# module.net
KiCad netlist of a schematic drawn in EAGLE
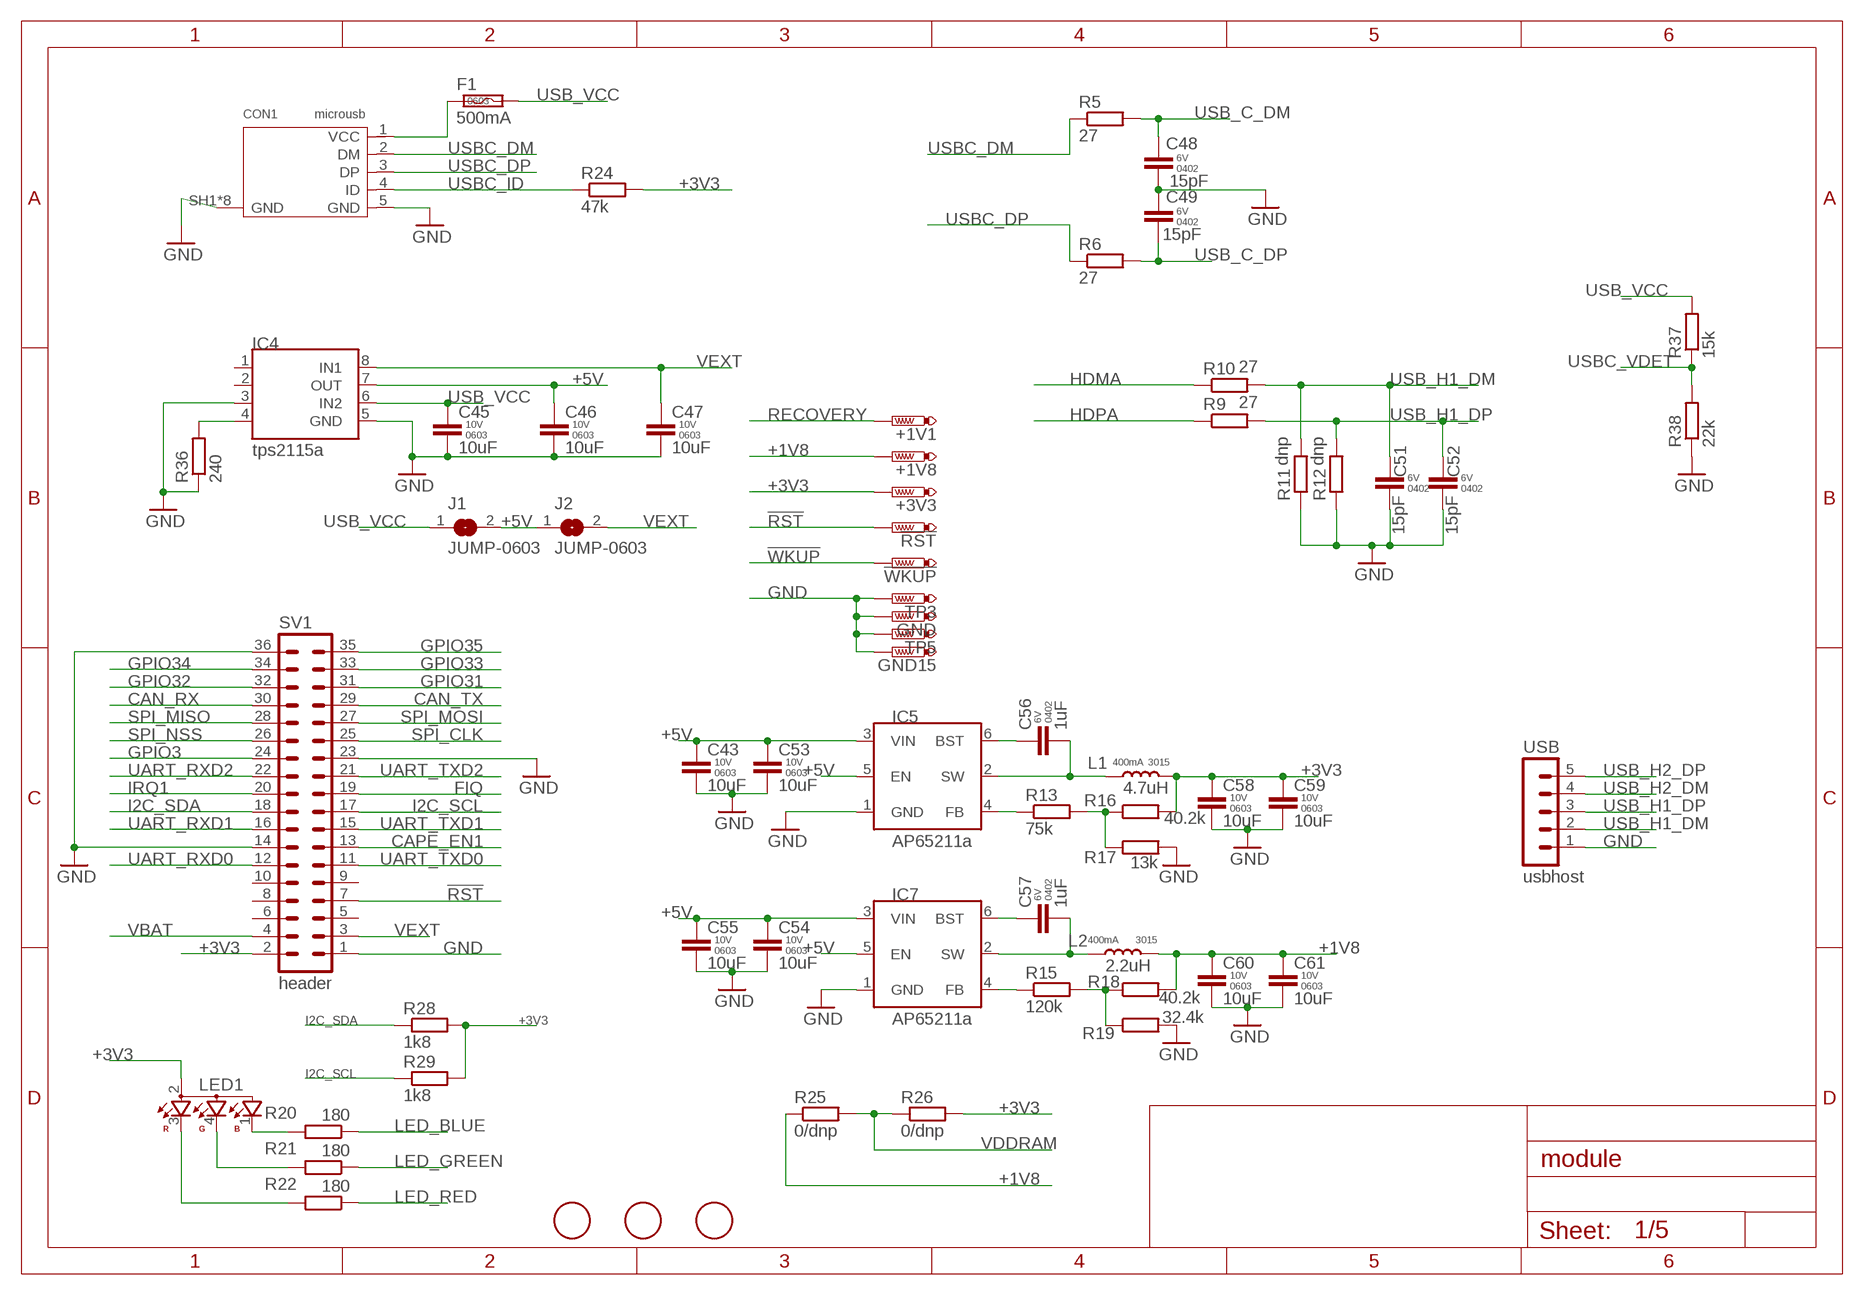
[diagram p0: schematic, sheet 1]
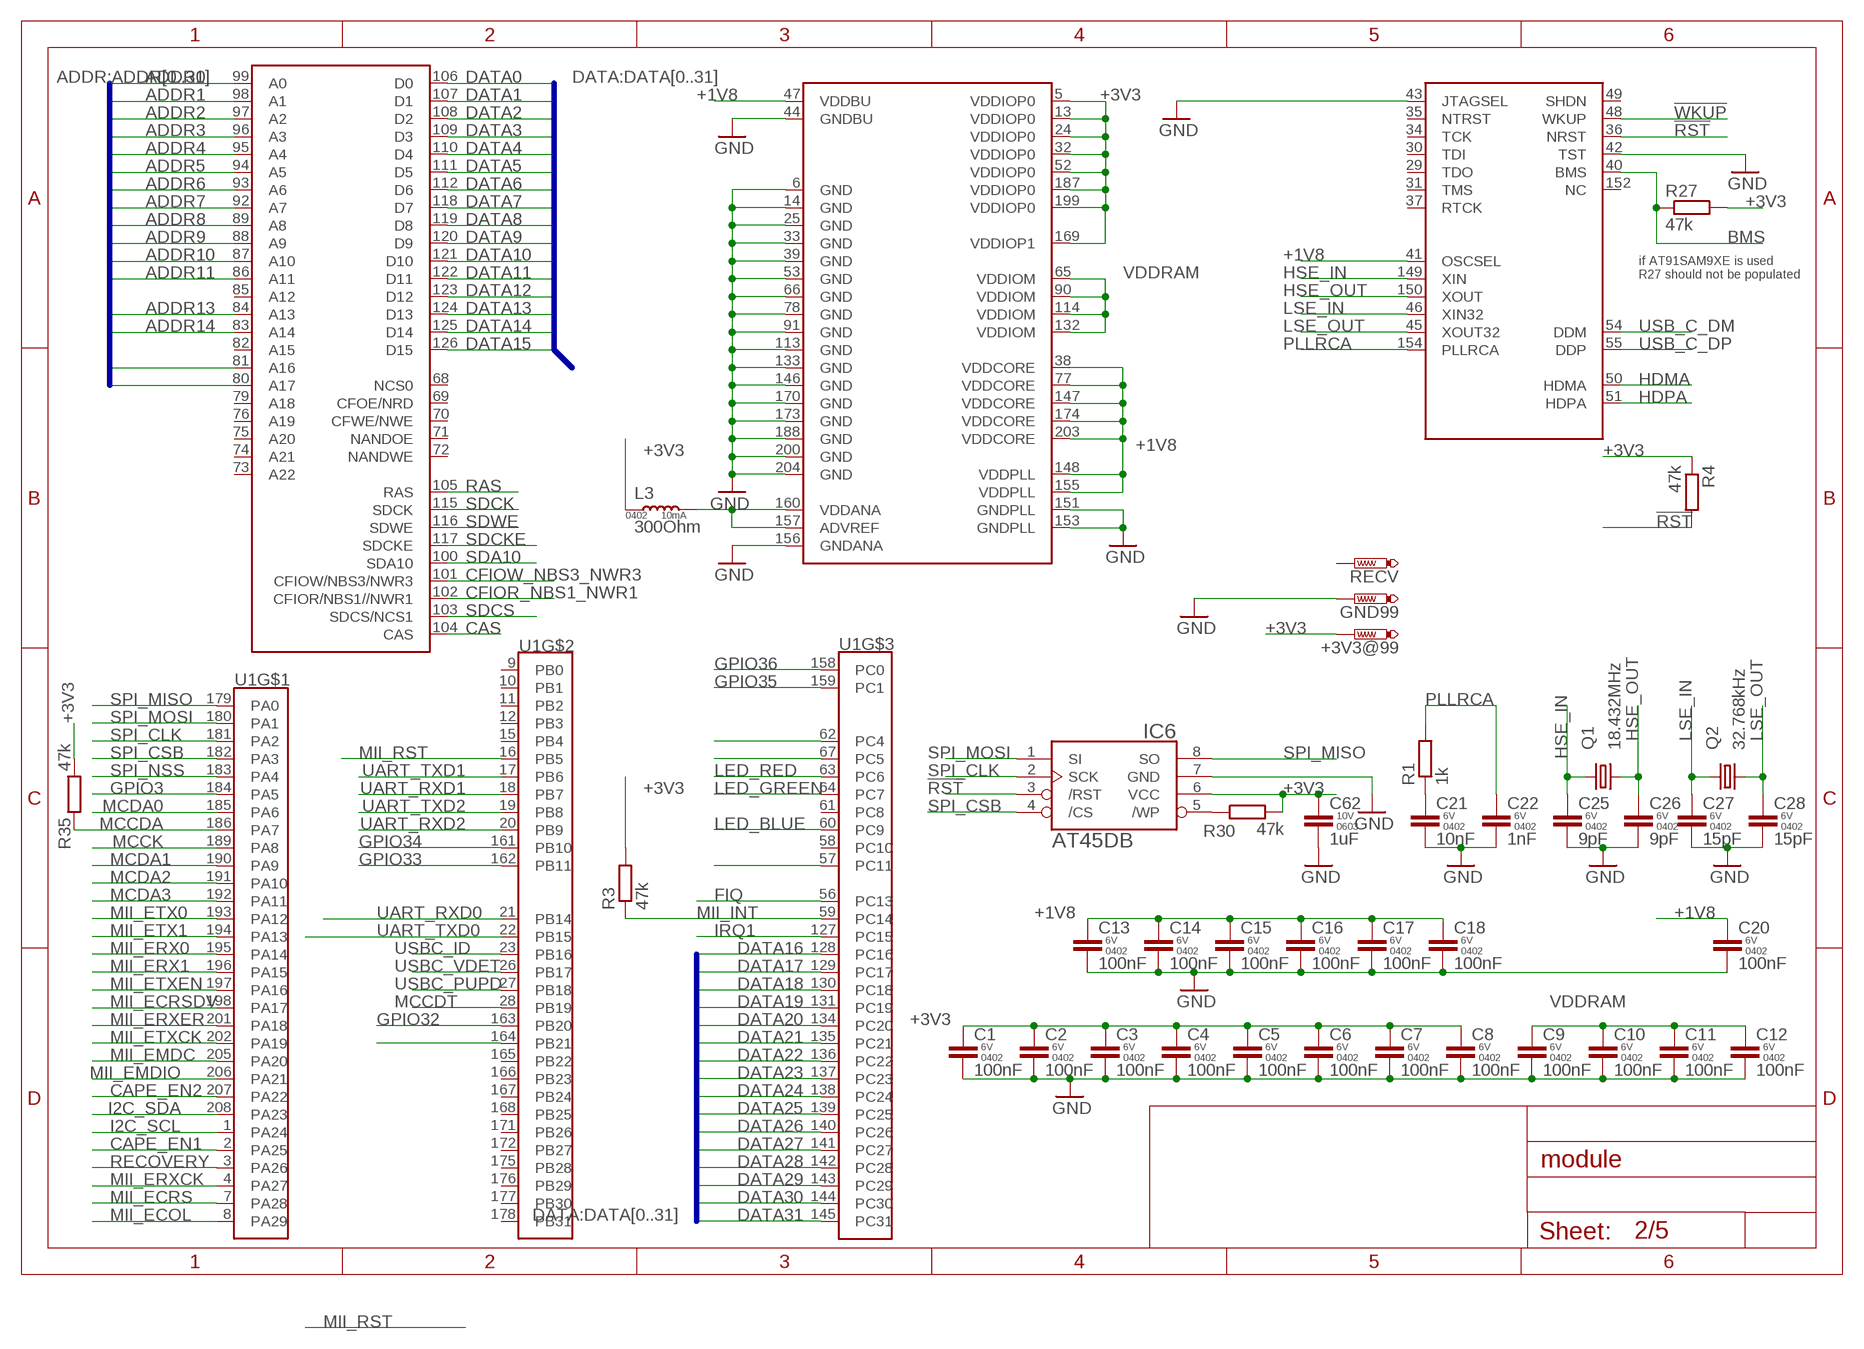
[diagram p1: schematic, sheet 2]
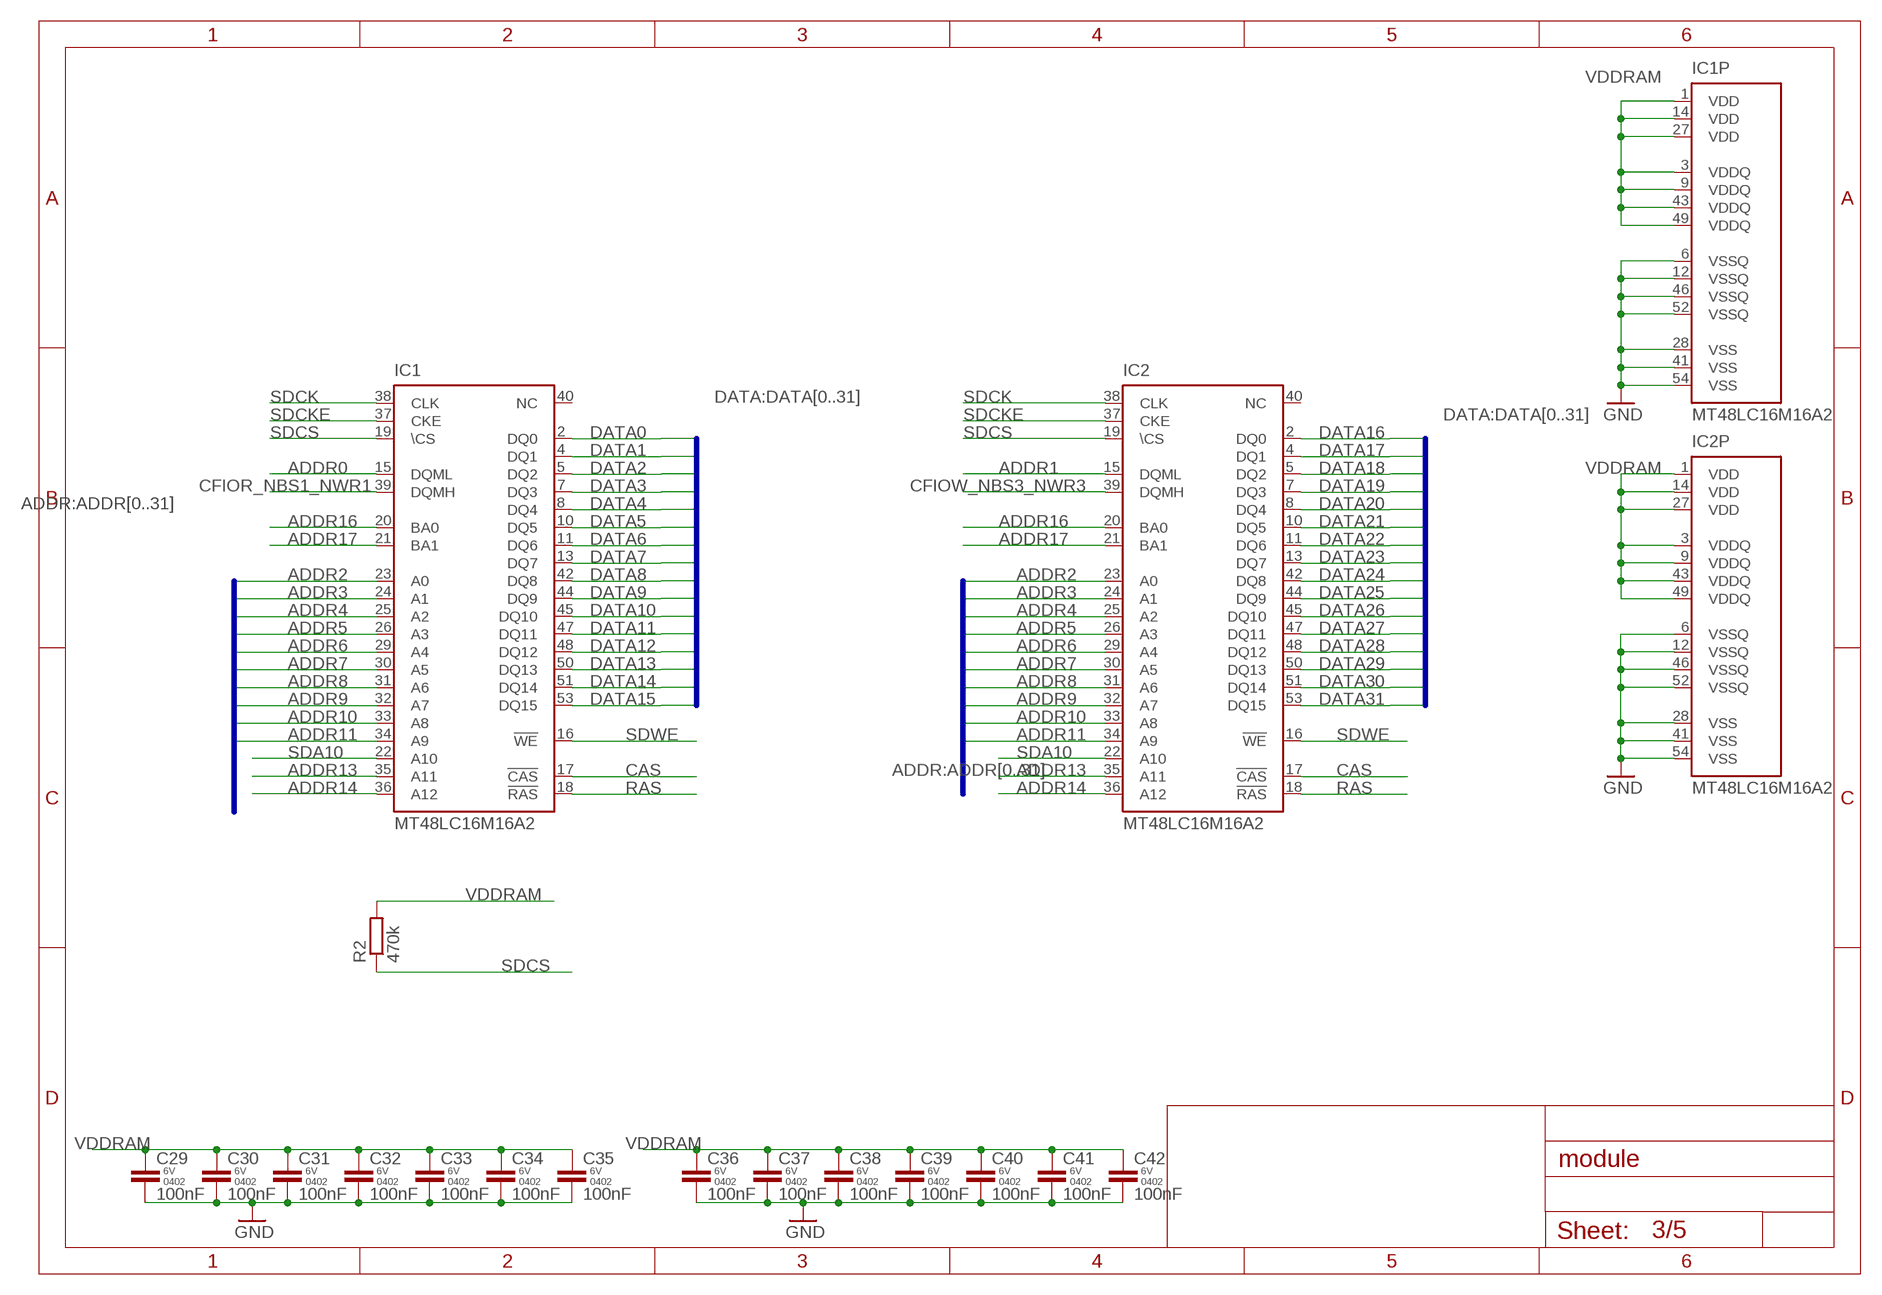
[diagram p2: schematic, sheet 3]
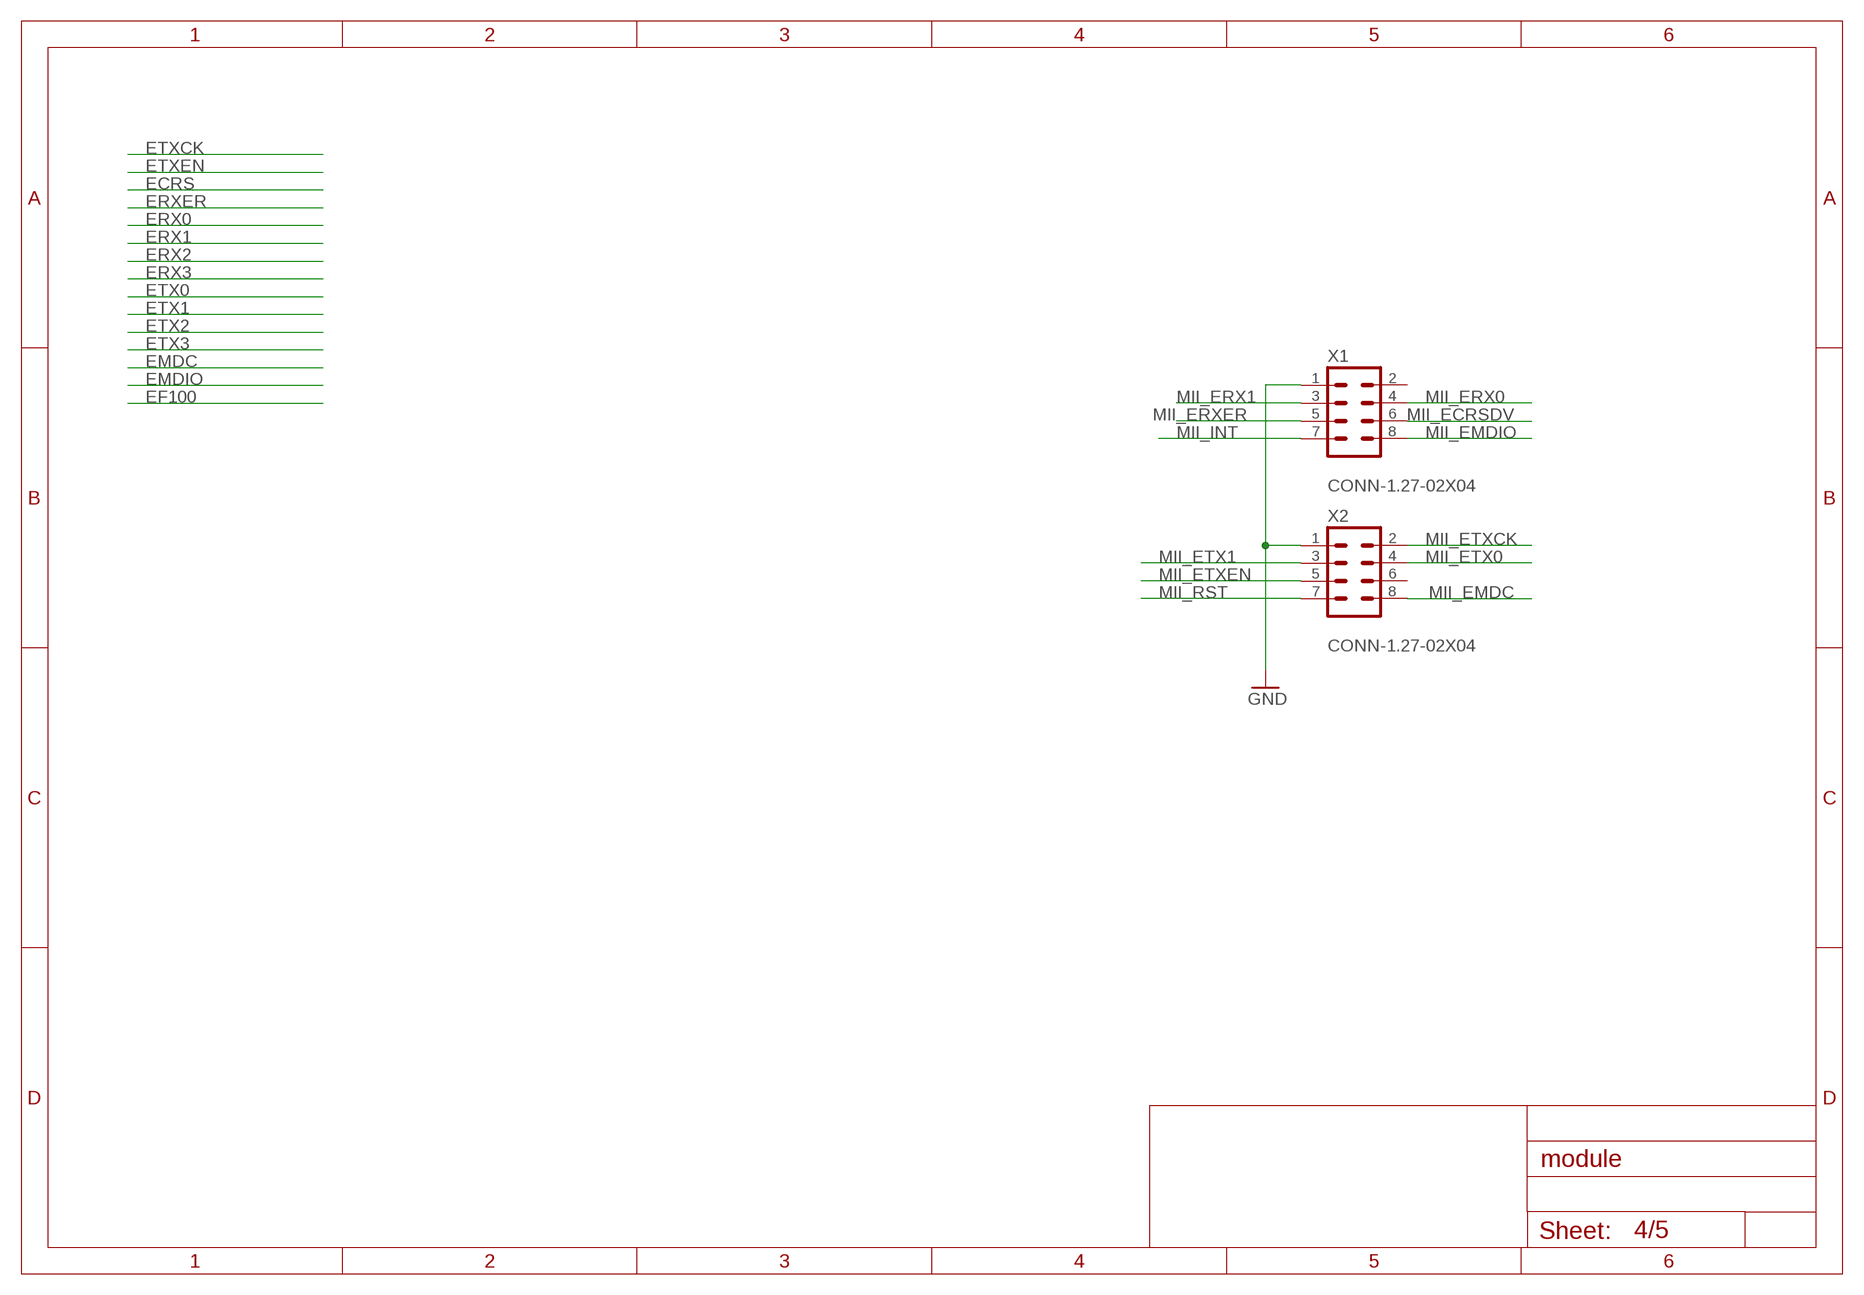
[diagram p3: schematic, sheet 4]
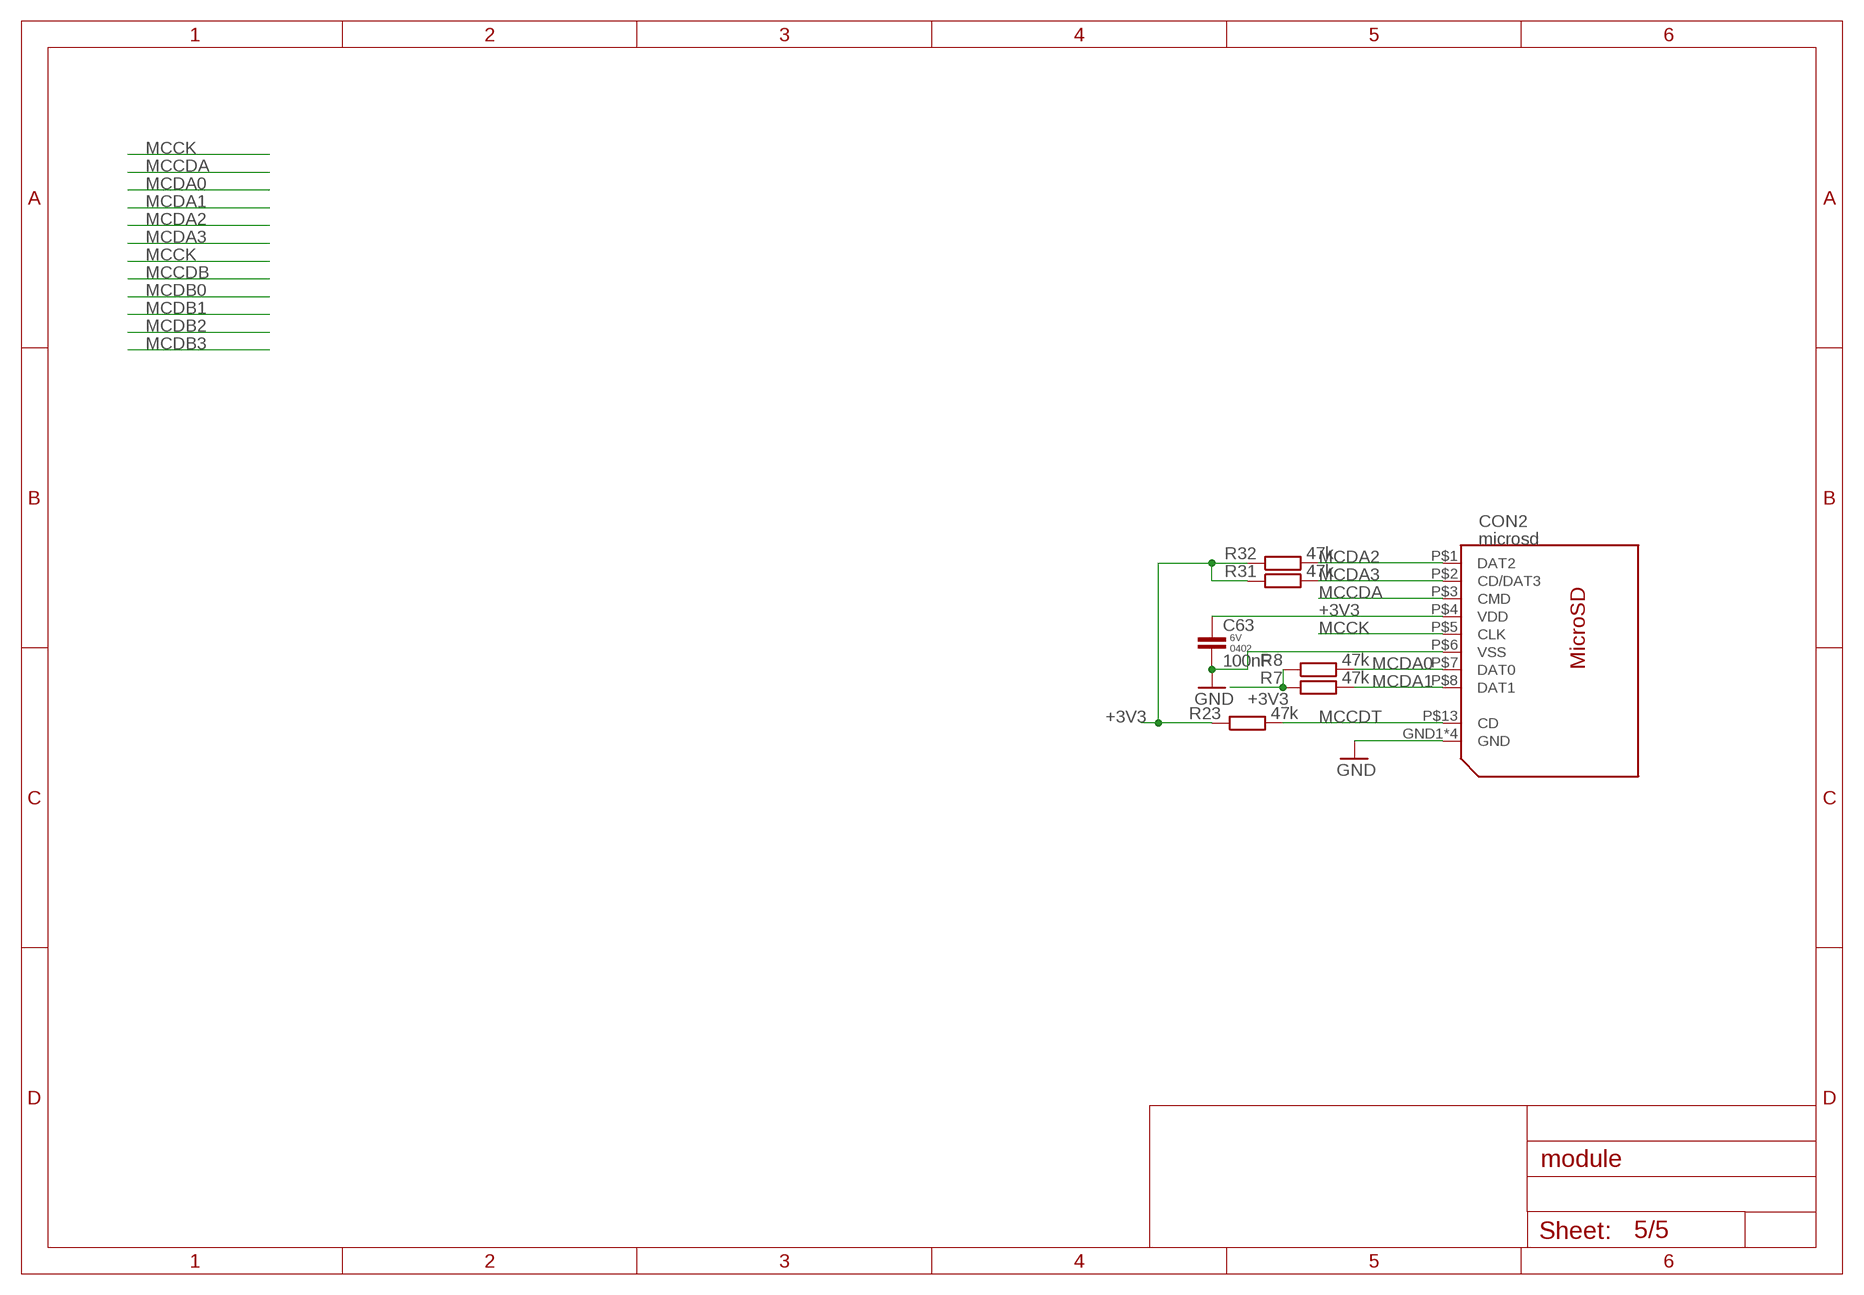
[diagram p4: schematic, sheet 5]

(export (version "E")
  (design (tool "Eeschema 10.0.6"))
  (components
    (comp (ref "C29")
      (value "100nF")
      (footprint "eagle-import:C0402K")
      (fields (field (name "RATING") "6V") (field (name "PACKAGE") "0402"))
      (libsource (lib "eagle-import") (part "CAP-0402"))
    )
    (comp (ref "C30")
      (value "100nF")
      (footprint "eagle-import:C0402K")
      (fields (field (name "RATING") "6V") (field (name "PACKAGE") "0402"))
      (libsource (lib "eagle-import") (part "CAP-0402"))
    )
    (comp (ref "C31")
      (value "100nF")
      (footprint "eagle-import:C0402K")
      (fields (field (name "RATING") "6V") (field (name "PACKAGE") "0402"))
      (libsource (lib "eagle-import") (part "CAP-0402"))
    )
    (comp (ref "C32")
      (value "100nF")
      (footprint "eagle-import:C0402K")
      (fields (field (name "RATING") "6V") (field (name "PACKAGE") "0402"))
      (libsource (lib "eagle-import") (part "CAP-0402"))
    )
    (comp (ref "C33")
      (value "100nF")
      (footprint "eagle-import:C0402K")
      (fields (field (name "RATING") "6V") (field (name "PACKAGE") "0402"))
      (libsource (lib "eagle-import") (part "CAP-0402"))
    )
    (comp (ref "C34")
      (value "100nF")
      (footprint "eagle-import:C0402K")
      (fields (field (name "RATING") "6V") (field (name "PACKAGE") "0402"))
      (libsource (lib "eagle-import") (part "CAP-0402"))
    )
    (comp (ref "C35")
      (value "100nF")
      (footprint "eagle-import:C0402K")
      (fields (field (name "RATING") "6V") (field (name "PACKAGE") "0402"))
      (libsource (lib "eagle-import") (part "CAP-0402"))
    )
    (comp (ref "C36")
      (value "100nF")
      (footprint "eagle-import:C0402K")
      (fields (field (name "RATING") "6V") (field (name "PACKAGE") "0402"))
      (libsource (lib "eagle-import") (part "CAP-0402"))
    )
    (comp (ref "C37")
      (value "100nF")
      (footprint "eagle-import:C0402K")
      (fields (field (name "RATING") "6V") (field (name "PACKAGE") "0402"))
      (libsource (lib "eagle-import") (part "CAP-0402"))
    )
    (comp (ref "C38")
      (value "100nF")
      (footprint "eagle-import:C0402K")
      (fields (field (name "RATING") "6V") (field (name "PACKAGE") "0402"))
      (libsource (lib "eagle-import") (part "CAP-0402"))
    )
    (comp (ref "C39")
      (value "100nF")
      (footprint "eagle-import:C0402K")
      (fields (field (name "RATING") "6V") (field (name "PACKAGE") "0402"))
      (libsource (lib "eagle-import") (part "CAP-0402"))
    )
    (comp (ref "C40")
      (value "100nF")
      (footprint "eagle-import:C0402K")
      (fields (field (name "RATING") "6V") (field (name "PACKAGE") "0402"))
      (libsource (lib "eagle-import") (part "CAP-0402"))
    )
    (comp (ref "C41")
      (value "100nF")
      (footprint "eagle-import:C0402K")
      (fields (field (name "RATING") "6V") (field (name "PACKAGE") "0402"))
      (libsource (lib "eagle-import") (part "CAP-0402"))
    )
    (comp (ref "C42")
      (value "100nF")
      (footprint "eagle-import:C0402K")
      (fields (field (name "RATING") "6V") (field (name "PACKAGE") "0402"))
      (libsource (lib "eagle-import") (part "CAP-0402"))
    )
    (comp (ref "IC1")
      (value "MT48LC16M16A2")
      (footprint "eagle-import:TSOP54-400")
      (libsource (lib "eagle-import") (part "MT48LC16M16A2"))
    )
    (comp (ref "IC2")
      (value "MT48LC16M16A2")
      (footprint "eagle-import:TSOP54-400")
      (libsource (lib "eagle-import") (part "MT48LC16M16A2"))
    )
    (comp (ref "R2")
      (value "470k")
      (footprint "eagle-import:R0402")
      (libsource (lib "eagle-import") (part "R-EU_R0402"))
    )
    (comp (ref "!RST")
      (value "PTR1B1,27")
      (footprint "eagle-import:B1,27")
      (libsource (lib "eagle-import") (part "PTR1B1,27"))
    )
    (comp (ref "!WKUP")
      (value "PTR1B1,27")
      (footprint "eagle-import:B1,27")
      (libsource (lib "eagle-import") (part "PTR1B1,27"))
    )
    (comp (ref "+1V1")
      (value "PTR1B1,27")
      (footprint "eagle-import:B1,27")
      (libsource (lib "eagle-import") (part "PTR1B1,27"))
    )
    (comp (ref "+1V8")
      (value "PTR1B1,27")
      (footprint "eagle-import:B1,27")
      (libsource (lib "eagle-import") (part "PTR1B1,27"))
    )
    (comp (ref "+3V3")
      (value "PTR1B1,27")
      (footprint "eagle-import:B1,27")
      (libsource (lib "eagle-import") (part "PTR1B1,27"))
    )
    (comp (ref "C43")
      (value "10uF")
      (footprint "eagle-import:C0603")
      (fields (field (name "RATING") "10V") (field (name "PACKAGE") "0603"))
      (libsource (lib "eagle-import") (part "CAP-0603"))
    )
    (comp (ref "C45")
      (value "10uF")
      (footprint "eagle-import:C0603")
      (fields (field (name "RATING") "10V") (field (name "PACKAGE") "0603"))
      (libsource (lib "eagle-import") (part "CAP-0603"))
    )
    (comp (ref "C46")
      (value "10uF")
      (footprint "eagle-import:C0603")
      (fields (field (name "RATING") "10V") (field (name "PACKAGE") "0603"))
      (libsource (lib "eagle-import") (part "CAP-0603"))
    )
    (comp (ref "C47")
      (value "10uF")
      (footprint "eagle-import:C0603")
      (fields (field (name "RATING") "10V") (field (name "PACKAGE") "0603"))
      (libsource (lib "eagle-import") (part "CAP-0603"))
    )
    (comp (ref "C48")
      (value "15pF")
      (footprint "eagle-import:C0402K")
      (fields (field (name "RATING") "6V") (field (name "PACKAGE") "0402"))
      (libsource (lib "eagle-import") (part "CAP-0402"))
    )
    (comp (ref "C49")
      (value "15pF")
      (footprint "eagle-import:C0402K")
      (fields (field (name "RATING") "6V") (field (name "PACKAGE") "0402"))
      (libsource (lib "eagle-import") (part "CAP-0402"))
    )
    (comp (ref "C51")
      (value "15pF")
      (footprint "eagle-import:C0402K")
      (fields (field (name "RATING") "6V") (field (name "PACKAGE") "0402"))
      (libsource (lib "eagle-import") (part "CAP-0402"))
    )
    (comp (ref "C52")
      (value "15pF")
      (footprint "eagle-import:C0402K")
      (fields (field (name "RATING") "6V") (field (name "PACKAGE") "0402"))
      (libsource (lib "eagle-import") (part "CAP-0402"))
    )
    (comp (ref "C53")
      (value "10uF")
      (footprint "eagle-import:C0603")
      (fields (field (name "RATING") "10V") (field (name "PACKAGE") "0603"))
      (libsource (lib "eagle-import") (part "CAP-0603"))
    )
    (comp (ref "C54")
      (value "10uF")
      (footprint "eagle-import:C0603")
      (fields (field (name "RATING") "10V") (field (name "PACKAGE") "0603"))
      (libsource (lib "eagle-import") (part "CAP-0603"))
    )
    (comp (ref "C55")
      (value "10uF")
      (footprint "eagle-import:C0603")
      (fields (field (name "RATING") "10V") (field (name "PACKAGE") "0603"))
      (libsource (lib "eagle-import") (part "CAP-0603"))
    )
    (comp (ref "C56")
      (value "1uF")
      (footprint "eagle-import:C0402K")
      (fields (field (name "RATING") "6V") (field (name "PACKAGE") "0402"))
      (libsource (lib "eagle-import") (part "CAP-0402"))
    )
    (comp (ref "C57")
      (value "1uF")
      (footprint "eagle-import:C0402K")
      (fields (field (name "RATING") "6V") (field (name "PACKAGE") "0402"))
      (libsource (lib "eagle-import") (part "CAP-0402"))
    )
    (comp (ref "C58")
      (value "10uF")
      (footprint "eagle-import:C0603")
      (fields (field (name "RATING") "10V") (field (name "PACKAGE") "0603"))
      (libsource (lib "eagle-import") (part "CAP-0603"))
    )
    (comp (ref "C59")
      (value "10uF")
      (footprint "eagle-import:C0603")
      (fields (field (name "RATING") "10V") (field (name "PACKAGE") "0603"))
      (libsource (lib "eagle-import") (part "CAP-0603"))
    )
    (comp (ref "C60")
      (value "10uF")
      (footprint "eagle-import:C0603")
      (fields (field (name "RATING") "10V") (field (name "PACKAGE") "0603"))
      (libsource (lib "eagle-import") (part "CAP-0603"))
    )
    (comp (ref "C61")
      (value "10uF")
      (footprint "eagle-import:C0603")
      (fields (field (name "RATING") "10V") (field (name "PACKAGE") "0603"))
      (libsource (lib "eagle-import") (part "CAP-0603"))
    )
    (comp (ref "CON1")
      (value "microusb")
      (footprint "eagle-import:10118194")
      (libsource (lib "eagle-import") (part "10118194-0001LF"))
    )
    (comp (ref "F1")
      (value "500mA")
      (footprint "eagle-import:F0603")
      (fields (field (name "PACKAGE") "0603"))
      (libsource (lib "eagle-import") (part "FUSE-PTC-0603"))
    )
    (comp (ref "GND")
      (value "PTR1B1,27")
      (footprint "eagle-import:B1,27")
      (libsource (lib "eagle-import") (part "PTR1B1,27"))
    )
    (comp (ref "GND15")
      (value "PTR1B1,27")
      (footprint "eagle-import:B1,27")
      (libsource (lib "eagle-import") (part "PTR1B1,27"))
    )
    (comp (ref "IC4")
      (value "tps2115a")
      (footprint "eagle-import:TSSOP8")
      (libsource (lib "eagle-import") (part "TPS2115A"))
    )
    (comp (ref "IC5")
      (value "AP65211")
      (footprint "eagle-import:SOT95P280X110-6")
      (libsource (lib "eagle-import") (part "AP65211"))
    )
    (comp (ref "IC7")
      (value "AP65211")
      (footprint "eagle-import:SOT95P280X110-6")
      (libsource (lib "eagle-import") (part "AP65211"))
    )
    (comp (ref "J1")
      (value "JUMP-0603")
      (footprint "eagle-import:C0603")
      (libsource (lib "eagle-import") (part "JUMP-0603"))
    )
    (comp (ref "J2")
      (value "JUMP-0603")
      (footprint "eagle-import:C0603")
      (libsource (lib "eagle-import") (part "JUMP-0603"))
    )
    (comp (ref "L1")
      (value "4.7uH")
      (footprint "eagle-import:L3230M")
      (fields (field (name "PACKAGE") "3015") (field (name "CURRENT") "400mA"))
      (libsource (lib "eagle-import") (part "DJNR3015"))
    )
    (comp (ref "L2")
      (value "2.2uH")
      (footprint "eagle-import:L3230M")
      (fields (field (name "PACKAGE") "3015") (field (name "CURRENT") "400mA"))
      (libsource (lib "eagle-import") (part "DJNR3015"))
    )
    (comp (ref "LED1")
      (value "OSTB1204C1E")
      (footprint "eagle-import:321015RGB")
      (libsource (lib "eagle-import") (part "OSTB1204C1E"))
    )
    (comp (ref "R5")
      (value "27")
      (footprint "eagle-import:R0402")
      (libsource (lib "eagle-import") (part "R-EU_R0402"))
    )
    (comp (ref "R6")
      (value "27")
      (footprint "eagle-import:R0402")
      (libsource (lib "eagle-import") (part "R-EU_R0402"))
    )
    (comp (ref "R9")
      (value "27")
      (footprint "eagle-import:R0402")
      (libsource (lib "eagle-import") (part "R-EU_R0402"))
    )
    (comp (ref "R10")
      (value "27")
      (footprint "eagle-import:R0402")
      (libsource (lib "eagle-import") (part "R-EU_R0402"))
    )
    (comp (ref "R11")
      (value "dnp")
      (footprint "eagle-import:R0402")
      (libsource (lib "eagle-import") (part "R-EU_R0402"))
    )
    (comp (ref "R12")
      (value "dnp")
      (footprint "eagle-import:R0402")
      (libsource (lib "eagle-import") (part "R-EU_R0402"))
    )
    (comp (ref "R13")
      (value "75k")
      (footprint "eagle-import:R0402")
      (libsource (lib "eagle-import") (part "R-EU_R0402"))
    )
    (comp (ref "R15")
      (value "120k")
      (footprint "eagle-import:R0402")
      (libsource (lib "eagle-import") (part "R-EU_R0402"))
    )
    (comp (ref "R16")
      (value "40.2k")
      (footprint "eagle-import:R0402")
      (libsource (lib "eagle-import") (part "R-EU_R0402"))
    )
    (comp (ref "R17")
      (value "13k")
      (footprint "eagle-import:R0402")
      (libsource (lib "eagle-import") (part "R-EU_R0402"))
    )
    (comp (ref "R18")
      (value "40.2k")
      (footprint "eagle-import:R0402")
      (libsource (lib "eagle-import") (part "R-EU_R0402"))
    )
    (comp (ref "R19")
      (value "32.4k")
      (footprint "eagle-import:R0402")
      (libsource (lib "eagle-import") (part "R-EU_R0402"))
    )
    (comp (ref "R20")
      (value "180")
      (footprint "eagle-import:R0402")
      (libsource (lib "eagle-import") (part "R-EU_R0402"))
    )
    (comp (ref "R21")
      (value "180")
      (footprint "eagle-import:R0402")
      (libsource (lib "eagle-import") (part "R-EU_R0402"))
    )
    (comp (ref "R22")
      (value "180")
      (footprint "eagle-import:R0402")
      (libsource (lib "eagle-import") (part "R-EU_R0402"))
    )
    (comp (ref "R24")
      (value "47k")
      (footprint "eagle-import:R0402")
      (libsource (lib "eagle-import") (part "R-EU_R0402"))
    )
    (comp (ref "R25")
      (value "0/dnp")
      (footprint "eagle-import:R0603")
      (libsource (lib "eagle-import") (part "R-EU_R0603"))
    )
    (comp (ref "R26")
      (value "0/dnp")
      (footprint "eagle-import:R0603")
      (libsource (lib "eagle-import") (part "R-EU_R0603"))
    )
    (comp (ref "R28")
      (value "1k8")
      (footprint "eagle-import:R0402")
      (libsource (lib "eagle-import") (part "R-EU_R0402"))
    )
    (comp (ref "R29")
      (value "1k8")
      (footprint "eagle-import:R0402")
      (libsource (lib "eagle-import") (part "R-EU_R0402"))
    )
    (comp (ref "R36")
      (value "240")
      (footprint "eagle-import:R0402")
      (libsource (lib "eagle-import") (part "R-EU_R0402"))
    )
    (comp (ref "R37")
      (value "15k")
      (footprint "eagle-import:R0402")
      (libsource (lib "eagle-import") (part "R-EU_R0402"))
    )
    (comp (ref "R38")
      (value "22k")
      (footprint "eagle-import:R0402")
      (libsource (lib "eagle-import") (part "R-EU_R0402"))
    )
    (comp (ref "SV1")
      (value "header")
      (footprint "eagle-import:MA18-2")
      (libsource (lib "eagle-import") (part "MA18-2"))
    )
    (comp (ref "TP3")
      (value "PTR1B1,27")
      (footprint "eagle-import:B1,27")
      (libsource (lib "eagle-import") (part "PTR1B1,27"))
    )
    (comp (ref "TP5")
      (value "PTR1B1,27")
      (footprint "eagle-import:B1,27")
      (libsource (lib "eagle-import") (part "PTR1B1,27"))
    )
    (comp (ref "U$1")
      (value "FIDUCIAL")
      (footprint "eagle-import:FIDUCIAL_1MM")
      (libsource (lib "eagle-import") (part "FIDUCIAL"))
    )
    (comp (ref "U$2")
      (value "FIDUCIAL")
      (footprint "eagle-import:FIDUCIAL_1MM")
      (libsource (lib "eagle-import") (part "FIDUCIAL"))
    )
    (comp (ref "U$3")
      (value "FIDUCIAL")
      (footprint "eagle-import:FIDUCIAL_1MM")
      (libsource (lib "eagle-import") (part "FIDUCIAL"))
    )
    (comp (ref "USB")
      (value "usbhost")
      (footprint "eagle-import:MA05-1")
      (libsource (lib "eagle-import") (part "MA05-1"))
    )
    (comp (ref "X1")
      (value "CONN-1.27-02X04")
      (footprint "eagle-import:050_610_HN-5_10")
      (libsource (lib "eagle-import") (part "CONN-1.27-02X04"))
    )
    (comp (ref "X2")
      (value "CONN-1.27-02X04")
      (footprint "eagle-import:050_610_HN-5_10")
      (libsource (lib "eagle-import") (part "CONN-1.27-02X04"))
    )
    (comp (ref "C63")
      (value "100nF")
      (footprint "eagle-import:C0402K")
      (fields (field (name "RATING") "6V") (field (name "PACKAGE") "0402"))
      (libsource (lib "eagle-import") (part "CAP-0402"))
    )
    (comp (ref "CON2")
      (value "microsd")
      (footprint "eagle-import:112J")
      (libsource (lib "eagle-import") (part "112J-TXAR"))
    )
    (comp (ref "R7")
      (value "47k")
      (footprint "eagle-import:R0402")
      (libsource (lib "eagle-import") (part "R-EU_R0402"))
    )
    (comp (ref "R8")
      (value "47k")
      (footprint "eagle-import:R0402")
      (libsource (lib "eagle-import") (part "R-EU_R0402"))
    )
    (comp (ref "R23")
      (value "47k")
      (footprint "eagle-import:R0402")
      (libsource (lib "eagle-import") (part "R-EU_R0402"))
    )
    (comp (ref "R31")
      (value "47k")
      (footprint "eagle-import:R0402")
      (libsource (lib "eagle-import") (part "R-EU_R0402"))
    )
    (comp (ref "R32")
      (value "47k")
      (footprint "eagle-import:R0402")
      (libsource (lib "eagle-import") (part "R-EU_R0402"))
    )
    (comp (ref "+3V3@99")
      (value "PTR1B1,27")
      (footprint "eagle-import:B1,27")
      (libsource (lib "eagle-import") (part "PTR1B1,27"))
    )
    (comp (ref "C1")
      (value "100nF")
      (footprint "eagle-import:C0402K")
      (fields (field (name "RATING") "6V") (field (name "PACKAGE") "0402"))
      (libsource (lib "eagle-import") (part "CAP-0402"))
    )
    (comp (ref "C2")
      (value "100nF")
      (footprint "eagle-import:C0402K")
      (fields (field (name "RATING") "6V") (field (name "PACKAGE") "0402"))
      (libsource (lib "eagle-import") (part "CAP-0402"))
    )
    (comp (ref "C3")
      (value "100nF")
      (footprint "eagle-import:C0402K")
      (fields (field (name "RATING") "6V") (field (name "PACKAGE") "0402"))
      (libsource (lib "eagle-import") (part "CAP-0402"))
    )
    (comp (ref "C4")
      (value "100nF")
      (footprint "eagle-import:C0402K")
      (fields (field (name "RATING") "6V") (field (name "PACKAGE") "0402"))
      (libsource (lib "eagle-import") (part "CAP-0402"))
    )
    (comp (ref "C5")
      (value "100nF")
      (footprint "eagle-import:C0402K")
      (fields (field (name "RATING") "6V") (field (name "PACKAGE") "0402"))
      (libsource (lib "eagle-import") (part "CAP-0402"))
    )
    (comp (ref "C6")
      (value "100nF")
      (footprint "eagle-import:C0402K")
      (fields (field (name "RATING") "6V") (field (name "PACKAGE") "0402"))
      (libsource (lib "eagle-import") (part "CAP-0402"))
    )
    (comp (ref "C7")
      (value "100nF")
      (footprint "eagle-import:C0402K")
      (fields (field (name "RATING") "6V") (field (name "PACKAGE") "0402"))
      (libsource (lib "eagle-import") (part "CAP-0402"))
    )
    (comp (ref "C8")
      (value "100nF")
      (footprint "eagle-import:C0402K")
      (fields (field (name "RATING") "6V") (field (name "PACKAGE") "0402"))
      (libsource (lib "eagle-import") (part "CAP-0402"))
    )
    (comp (ref "C9")
      (value "100nF")
      (footprint "eagle-import:C0402K")
      (fields (field (name "RATING") "6V") (field (name "PACKAGE") "0402"))
      (libsource (lib "eagle-import") (part "CAP-0402"))
    )
    (comp (ref "C10")
      (value "100nF")
      (footprint "eagle-import:C0402K")
      (fields (field (name "RATING") "6V") (field (name "PACKAGE") "0402"))
      (libsource (lib "eagle-import") (part "CAP-0402"))
    )
    (comp (ref "C11")
      (value "100nF")
      (footprint "eagle-import:C0402K")
      (fields (field (name "RATING") "6V") (field (name "PACKAGE") "0402"))
      (libsource (lib "eagle-import") (part "CAP-0402"))
    )
    (comp (ref "C12")
      (value "100nF")
      (footprint "eagle-import:C0402K")
      (fields (field (name "RATING") "6V") (field (name "PACKAGE") "0402"))
      (libsource (lib "eagle-import") (part "CAP-0402"))
    )
    (comp (ref "C13")
      (value "100nF")
      (footprint "eagle-import:C0402K")
      (fields (field (name "RATING") "6V") (field (name "PACKAGE") "0402"))
      (libsource (lib "eagle-import") (part "CAP-0402"))
    )
    (comp (ref "C14")
      (value "100nF")
      (footprint "eagle-import:C0402K")
      (fields (field (name "RATING") "6V") (field (name "PACKAGE") "0402"))
      (libsource (lib "eagle-import") (part "CAP-0402"))
    )
    (comp (ref "C15")
      (value "100nF")
      (footprint "eagle-import:C0402K")
      (fields (field (name "RATING") "6V") (field (name "PACKAGE") "0402"))
      (libsource (lib "eagle-import") (part "CAP-0402"))
    )
    (comp (ref "C16")
      (value "100nF")
      (footprint "eagle-import:C0402K")
      (fields (field (name "RATING") "6V") (field (name "PACKAGE") "0402"))
      (libsource (lib "eagle-import") (part "CAP-0402"))
    )
    (comp (ref "C17")
      (value "100nF")
      (footprint "eagle-import:C0402K")
      (fields (field (name "RATING") "6V") (field (name "PACKAGE") "0402"))
      (libsource (lib "eagle-import") (part "CAP-0402"))
    )
    (comp (ref "C18")
      (value "100nF")
      (footprint "eagle-import:C0402K")
      (fields (field (name "RATING") "6V") (field (name "PACKAGE") "0402"))
      (libsource (lib "eagle-import") (part "CAP-0402"))
    )
    (comp (ref "C20")
      (value "100nF")
      (footprint "eagle-import:C0402K")
      (fields (field (name "RATING") "6V") (field (name "PACKAGE") "0402"))
      (libsource (lib "eagle-import") (part "CAP-0402"))
    )
    (comp (ref "C21")
      (value "10nF")
      (footprint "eagle-import:C0402K")
      (fields (field (name "RATING") "6V") (field (name "PACKAGE") "0402"))
      (libsource (lib "eagle-import") (part "CAP-0402"))
    )
    (comp (ref "C22")
      (value "1nF")
      (footprint "eagle-import:C0402K")
      (fields (field (name "RATING") "6V") (field (name "PACKAGE") "0402"))
      (libsource (lib "eagle-import") (part "CAP-0402"))
    )
    (comp (ref "C25")
      (value "9pF")
      (footprint "eagle-import:C0402K")
      (fields (field (name "RATING") "6V") (field (name "PACKAGE") "0402"))
      (libsource (lib "eagle-import") (part "CAP-0402"))
    )
    (comp (ref "C26")
      (value "9pF")
      (footprint "eagle-import:C0402K")
      (fields (field (name "RATING") "6V") (field (name "PACKAGE") "0402"))
      (libsource (lib "eagle-import") (part "CAP-0402"))
    )
    (comp (ref "C27")
      (value "15pF")
      (footprint "eagle-import:C0402K")
      (fields (field (name "RATING") "6V") (field (name "PACKAGE") "0402"))
      (libsource (lib "eagle-import") (part "CAP-0402"))
    )
    (comp (ref "C28")
      (value "15pF")
      (footprint "eagle-import:C0402K")
      (fields (field (name "RATING") "6V") (field (name "PACKAGE") "0402"))
      (libsource (lib "eagle-import") (part "CAP-0402"))
    )
    (comp (ref "C62")
      (value "1uF")
      (footprint "eagle-import:C0603")
      (fields (field (name "RATING") "10V") (field (name "PACKAGE") "0603"))
      (libsource (lib "eagle-import") (part "CAP-0603"))
    )
    (comp (ref "GND99")
      (value "PTR1B1,27")
      (footprint "eagle-import:B1,27")
      (libsource (lib "eagle-import") (part "PTR1B1,27"))
    )
    (comp (ref "IC6")
      (value "AT45DB-S")
      (footprint "eagle-import:SO08-208")
      (libsource (lib "eagle-import") (part "AT45DB-S"))
    )
    (comp (ref "L3")
      (value "300Ohm")
      (footprint "eagle-import:L0402")
      (fields (field (name "PACKAGE") "0402") (field (name "CURRENT") "10mA"))
      (libsource (lib "eagle-import") (part "IND-0402"))
    )
    (comp (ref "Q1")
      (value "18.432MHz")
      (footprint "eagle-import:3215")
      (libsource (lib "eagle-import") (part "3215-7"))
    )
    (comp (ref "Q2")
      (value "32.768kHz")
      (footprint "eagle-import:3215")
      (libsource (lib "eagle-import") (part "CFPX–217-NHT"))
    )
    (comp (ref "R1")
      (value "1k")
      (footprint "eagle-import:R0402")
      (libsource (lib "eagle-import") (part "R-EU_R0402"))
    )
    (comp (ref "R3")
      (value "47k")
      (footprint "eagle-import:R0402")
      (libsource (lib "eagle-import") (part "R-EU_R0402"))
    )
    (comp (ref "R4")
      (value "47k")
      (footprint "eagle-import:R0402")
      (libsource (lib "eagle-import") (part "R-EU_R0402"))
    )
    (comp (ref "R27")
      (value "47k")
      (footprint "eagle-import:R0402")
      (libsource (lib "eagle-import") (part "R-EU_R0402"))
    )
    (comp (ref "R30")
      (value "47k")
      (footprint "eagle-import:R0402")
      (libsource (lib "eagle-import") (part "R-EU_R0402"))
    )
    (comp (ref "R35")
      (value "47k")
      (footprint "eagle-import:R0402")
      (libsource (lib "eagle-import") (part "R-EU_R0402"))
    )
    (comp (ref "RECV")
      (value "PTR1B1,27")
      (footprint "eagle-import:B1,27")
      (libsource (lib "eagle-import") (part "PTR1B1,27"))
    )
    (comp (ref "U1")
      (value "AT91SAM9260-")
      (footprint "eagle-import:QFP50P3120X3120X410-208N")
      (libsource (lib "eagle-import") (part "AT91SAM9260-"))
    )
  )
  (nets
    (net (code "97") (name "+1V8") (class "Default")
      (node (ref "+1V8") (pin "TP") (pinfunction "TP_TP") (pintype "input"))
      (node (ref "C13") (pin "1") (pinfunction "1_1") (pintype "passive"))
      (node (ref "C14") (pin "1") (pinfunction "1_1") (pintype "passive"))
      (node (ref "C15") (pin "1") (pinfunction "1_1") (pintype "passive"))
      (node (ref "C16") (pin "1") (pinfunction "1_1") (pintype "passive"))
      (node (ref "C17") (pin "1") (pinfunction "1_1") (pintype "passive"))
      (node (ref "C18") (pin "1") (pinfunction "1_1") (pintype "passive"))
      (node (ref "C20") (pin "1") (pinfunction "1_1") (pintype "passive"))
      (node (ref "C60") (pin "1") (pinfunction "1_1") (pintype "passive"))
      (node (ref "C61") (pin "1") (pinfunction "1_1") (pintype "passive"))
      (node (ref "L2") (pin "2") (pinfunction "2_2") (pintype "passive"))
      (node (ref "R18") (pin "2") (pinfunction "2_2") (pintype "passive"))
      (node (ref "R25") (pin "1") (pinfunction "1_1") (pintype "passive"))
      (node (ref "U1") (pin "147") (pinfunction "VDDCORE_147") (pintype "bidirectional"))
      (node (ref "U1") (pin "148") (pinfunction "VDDPLL_148") (pintype "bidirectional"))
      (node (ref "U1") (pin "155") (pinfunction "VDDPLL_155") (pintype "bidirectional"))
      (node (ref "U1") (pin "174") (pinfunction "VDDCORE_174") (pintype "bidirectional"))
      (node (ref "U1") (pin "203") (pinfunction "VDDCORE_203") (pintype "bidirectional"))
      (node (ref "U1") (pin "38") (pinfunction "VDDCORE_38") (pintype "bidirectional"))
      (node (ref "U1") (pin "41") (pinfunction "OSCSEL_41") (pintype "bidirectional"))
      (node (ref "U1") (pin "47") (pinfunction "VDDBU_47") (pintype "bidirectional"))
      (node (ref "U1") (pin "77") (pinfunction "VDDCORE_77") (pintype "bidirectional"))
    )
    (net (code "98") (name "+3V3") (class "Default")
      (node (ref "+3V3") (pin "TP") (pinfunction "TP_TP") (pintype "input"))
      (node (ref "+3V3@99") (pin "TP") (pinfunction "TP_TP") (pintype "input"))
      (node (ref "C1") (pin "1") (pinfunction "1_1") (pintype "passive"))
      (node (ref "C2") (pin "1") (pinfunction "1_1") (pintype "passive"))
      (node (ref "C3") (pin "1") (pinfunction "1_1") (pintype "passive"))
      (node (ref "C4") (pin "1") (pinfunction "1_1") (pintype "passive"))
      (node (ref "C5") (pin "1") (pinfunction "1_1") (pintype "passive"))
      (node (ref "C58") (pin "1") (pinfunction "1_1") (pintype "passive"))
      (node (ref "C59") (pin "1") (pinfunction "1_1") (pintype "passive"))
      (node (ref "C6") (pin "1") (pinfunction "1_1") (pintype "passive"))
      (node (ref "C62") (pin "1") (pinfunction "1_1") (pintype "passive"))
      (node (ref "C63") (pin "1") (pinfunction "1_1") (pintype "passive"))
      (node (ref "C7") (pin "1") (pinfunction "1_1") (pintype "passive"))
      (node (ref "C8") (pin "1") (pinfunction "1_1") (pintype "passive"))
      (node (ref "CON2") (pin "P$4") (pinfunction "VDD_P$4") (pintype "input"))
      (node (ref "IC6") (pin "6") (pinfunction "VCC_6") (pintype "power_in"))
      (node (ref "L1") (pin "2") (pinfunction "2_2") (pintype "passive"))
      (node (ref "L3") (pin "1") (pinfunction "1_1") (pintype "passive"))
      (node (ref "LED1") (pin "2") (pinfunction "2_2") (pintype "passive"))
      (node (ref "R16") (pin "2") (pinfunction "2_2") (pintype "passive"))
      (node (ref "R23") (pin "1") (pinfunction "1_1") (pintype "passive"))
      (node (ref "R24") (pin "2") (pinfunction "2_2") (pintype "passive"))
      (node (ref "R26") (pin "2") (pinfunction "2_2") (pintype "passive"))
      (node (ref "R27") (pin "2") (pinfunction "2_2") (pintype "passive"))
      (node (ref "R28") (pin "2") (pinfunction "2_2") (pintype "passive"))
      (node (ref "R29") (pin "2") (pinfunction "2_2") (pintype "passive"))
      (node (ref "R3") (pin "2") (pinfunction "2_2") (pintype "passive"))
      (node (ref "R30") (pin "2") (pinfunction "2_2") (pintype "passive"))
      (node (ref "R31") (pin "1") (pinfunction "1_1") (pintype "passive"))
      (node (ref "R32") (pin "1") (pinfunction "1_1") (pintype "passive"))
      (node (ref "R35") (pin "2") (pinfunction "2_2") (pintype "passive"))
      (node (ref "R4") (pin "1") (pinfunction "1_1") (pintype "passive"))
      (node (ref "R7") (pin "1") (pinfunction "1_1") (pintype "passive"))
      (node (ref "R8") (pin "1") (pinfunction "1_1") (pintype "passive"))
      (node (ref "SV1") (pin "2") (pinfunction "2_2") (pintype "passive"))
      (node (ref "U1") (pin "13") (pinfunction "VDDIOP0_13") (pintype "bidirectional"))
      (node (ref "U1") (pin "169") (pinfunction "VDDIOP1_169") (pintype "bidirectional"))
      (node (ref "U1") (pin "187") (pinfunction "VDDIOP0_187") (pintype "bidirectional"))
      (node (ref "U1") (pin "199") (pinfunction "VDDIOP0_199") (pintype "bidirectional"))
      (node (ref "U1") (pin "24") (pinfunction "VDDIOP0_24") (pintype "bidirectional"))
      (node (ref "U1") (pin "32") (pinfunction "VDDIOP0_32") (pintype "bidirectional"))
      (node (ref "U1") (pin "5") (pinfunction "VDDIOP0_5") (pintype "bidirectional"))
      (node (ref "U1") (pin "52") (pinfunction "VDDIOP0_52") (pintype "bidirectional"))
    )
    (net (code "99") (name "+5V") (class "Default")
      (node (ref "C43") (pin "1") (pinfunction "1_1") (pintype "passive"))
      (node (ref "C46") (pin "1") (pinfunction "1_1") (pintype "passive"))
      (node (ref "C53") (pin "1") (pinfunction "1_1") (pintype "passive"))
      (node (ref "C54") (pin "1") (pinfunction "1_1") (pintype "passive"))
      (node (ref "C55") (pin "1") (pinfunction "1_1") (pintype "passive"))
      (node (ref "IC4") (pin "7") (pinfunction "OUT_7") (pintype "bidirectional"))
      (node (ref "IC5") (pin "3") (pinfunction "VIN_3") (pintype "bidirectional"))
      (node (ref "IC5") (pin "5") (pinfunction "EN_5") (pintype "bidirectional"))
      (node (ref "IC7") (pin "3") (pinfunction "VIN_3") (pintype "bidirectional"))
      (node (ref "IC7") (pin "5") (pinfunction "EN_5") (pintype "bidirectional"))
      (node (ref "J1") (pin "2") (pinfunction "2_2") (pintype "passive"))
      (node (ref "J2") (pin "1") (pinfunction "1_1") (pintype "passive"))
    )
    (net (code "103") (name "ADDR0") (class "Default")
      (node (ref "IC1") (pin "15") (pinfunction "DQML_15") (pintype "input"))
      (node (ref "U1") (pin "99") (pinfunction "A0_99") (pintype "bidirectional"))
    )
    (net (code "104") (name "ADDR1") (class "Default")
      (node (ref "IC2") (pin "15") (pinfunction "DQML_15") (pintype "input"))
      (node (ref "U1") (pin "98") (pinfunction "A1_98") (pintype "bidirectional"))
    )
    (net (code "105") (name "ADDR2") (class "Default")
      (node (ref "IC1") (pin "23") (pinfunction "A0_23") (pintype "input"))
      (node (ref "IC2") (pin "23") (pinfunction "A0_23") (pintype "input"))
      (node (ref "U1") (pin "97") (pinfunction "A2_97") (pintype "bidirectional"))
    )
    (net (code "106") (name "ADDR3") (class "Default")
      (node (ref "IC1") (pin "24") (pinfunction "A1_24") (pintype "input"))
      (node (ref "IC2") (pin "24") (pinfunction "A1_24") (pintype "input"))
      (node (ref "U1") (pin "96") (pinfunction "A3_96") (pintype "bidirectional"))
    )
    (net (code "107") (name "ADDR4") (class "Default")
      (node (ref "IC1") (pin "25") (pinfunction "A2_25") (pintype "input"))
      (node (ref "IC2") (pin "25") (pinfunction "A2_25") (pintype "input"))
      (node (ref "U1") (pin "95") (pinfunction "A4_95") (pintype "bidirectional"))
    )
    (net (code "108") (name "ADDR5") (class "Default")
      (node (ref "IC1") (pin "26") (pinfunction "A3_26") (pintype "input"))
      (node (ref "IC2") (pin "26") (pinfunction "A3_26") (pintype "input"))
      (node (ref "U1") (pin "94") (pinfunction "A5_94") (pintype "bidirectional"))
    )
    (net (code "109") (name "ADDR6") (class "Default")
      (node (ref "IC1") (pin "29") (pinfunction "A4_29") (pintype "input"))
      (node (ref "IC2") (pin "29") (pinfunction "A4_29") (pintype "input"))
      (node (ref "U1") (pin "93") (pinfunction "A6_93") (pintype "bidirectional"))
    )
    (net (code "110") (name "ADDR7") (class "Default")
      (node (ref "IC1") (pin "30") (pinfunction "A5_30") (pintype "input"))
      (node (ref "IC2") (pin "30") (pinfunction "A5_30") (pintype "input"))
      (node (ref "U1") (pin "92") (pinfunction "A7_92") (pintype "bidirectional"))
    )
    (net (code "111") (name "ADDR8") (class "Default")
      (node (ref "IC1") (pin "31") (pinfunction "A6_31") (pintype "input"))
      (node (ref "IC2") (pin "31") (pinfunction "A6_31") (pintype "input"))
      (node (ref "U1") (pin "89") (pinfunction "A8_89") (pintype "bidirectional"))
    )
    (net (code "112") (name "ADDR9") (class "Default")
      (node (ref "IC1") (pin "32") (pinfunction "A7_32") (pintype "input"))
      (node (ref "IC2") (pin "32") (pinfunction "A7_32") (pintype "input"))
      (node (ref "U1") (pin "88") (pinfunction "A9_88") (pintype "bidirectional"))
    )
    (net (code "113") (name "ADDR10") (class "Default")
      (node (ref "IC1") (pin "33") (pinfunction "A8_33") (pintype "input"))
      (node (ref "IC2") (pin "33") (pinfunction "A8_33") (pintype "input"))
      (node (ref "U1") (pin "87") (pinfunction "A10_87") (pintype "bidirectional"))
    )
    (net (code "114") (name "ADDR11") (class "Default")
      (node (ref "IC1") (pin "34") (pinfunction "A9_34") (pintype "input"))
      (node (ref "IC2") (pin "34") (pinfunction "A9_34") (pintype "input"))
      (node (ref "U1") (pin "86") (pinfunction "A11_86") (pintype "bidirectional"))
    )
    (net (code "115") (name "ADDR13") (class "Default")
      (node (ref "IC1") (pin "35") (pinfunction "A11_35") (pintype "input"))
      (node (ref "IC2") (pin "35") (pinfunction "A11_35") (pintype "input"))
      (node (ref "U1") (pin "84") (pinfunction "A13_84") (pintype "bidirectional"))
    )
    (net (code "116") (name "ADDR14") (class "Default")
      (node (ref "IC1") (pin "36") (pinfunction "A12_36") (pintype "input"))
      (node (ref "IC2") (pin "36") (pinfunction "A12_36") (pintype "input"))
      (node (ref "U1") (pin "83") (pinfunction "A14_83") (pintype "bidirectional"))
    )
    (net (code "117") (name "ADDR16") (class "Default")
      (node (ref "IC1") (pin "20") (pinfunction "BA0_20") (pintype "input"))
      (node (ref "IC2") (pin "20") (pinfunction "BA0_20") (pintype "input"))
      (node (ref "U1") (pin "81") (pinfunction "A16_81") (pintype "bidirectional"))
    )
    (net (code "118") (name "ADDR17") (class "Default")
      (node (ref "IC1") (pin "21") (pinfunction "BA1_21") (pintype "input"))
      (node (ref "IC2") (pin "21") (pinfunction "BA1_21") (pintype "input"))
      (node (ref "U1") (pin "80") (pinfunction "A17_80") (pintype "bidirectional"))
    )
    (net (code "119") (name "BMS") (class "Default")
      (node (ref "R27") (pin "1") (pinfunction "1_1") (pintype "passive"))
      (node (ref "U1") (pin "40") (pinfunction "BMS_40") (pintype "bidirectional"))
    )
    (net (code "120") (name "CAN_RX") (class "Default")
      (node (ref "SV1") (pin "30") (pinfunction "30_30") (pintype "passive"))
    )
    (net (code "121") (name "CAN_TX") (class "Default")
      (node (ref "SV1") (pin "29") (pinfunction "29_29") (pintype "passive"))
    )
    (net (code "122") (name "CAPE_EN1") (class "Default")
      (node (ref "SV1") (pin "13") (pinfunction "13_13") (pintype "passive"))
      (node (ref "U1") (pin "2") (pinfunction "PA25_2") (pintype "bidirectional"))
    )
    (net (code "123") (name "CAPE_EN2") (class "Default")
      (node (ref "U1") (pin "207") (pinfunction "PA22_207") (pintype "bidirectional"))
    )
    (net (code "124") (name "CAS") (class "Default")
      (node (ref "IC1") (pin "17") (pinfunction "~{CAS}_17") (pintype "input"))
      (node (ref "IC2") (pin "17") (pinfunction "~{CAS}_17") (pintype "input"))
      (node (ref "U1") (pin "104") (pinfunction "CAS_104") (pintype "bidirectional"))
    )
    (net (code "125") (name "CFIOR_NBS1_NWR1") (class "Default")
      (node (ref "IC1") (pin "39") (pinfunction "DQMH_39") (pintype "input"))
      (node (ref "U1") (pin "102") (pinfunction "CFIOR/NBS1//NWR1_102") (pintype "bidirectional"))
    )
    (net (code "126") (name "CFIOW_NBS3_NWR3") (class "Default")
      (node (ref "IC2") (pin "39") (pinfunction "DQMH_39") (pintype "input"))
      (node (ref "U1") (pin "101") (pinfunction "CFIOW/NBS3/NWR3_101") (pintype "bidirectional"))
    )
    (net (code "127") (name "DATA0") (class "Default")
      (node (ref "IC1") (pin "2") (pinfunction "DQ0_2") (pintype "tri_state"))
      (node (ref "U1") (pin "106") (pinfunction "D0_106") (pintype "bidirectional"))
    )
    (net (code "128") (name "DATA1") (class "Default")
      (node (ref "IC1") (pin "4") (pinfunction "DQ1_4") (pintype "tri_state"))
      (node (ref "U1") (pin "107") (pinfunction "D1_107") (pintype "bidirectional"))
    )
    (net (code "129") (name "DATA2") (class "Default")
      (node (ref "IC1") (pin "5") (pinfunction "DQ2_5") (pintype "tri_state"))
      (node (ref "U1") (pin "108") (pinfunction "D2_108") (pintype "bidirectional"))
    )
    (net (code "130") (name "DATA3") (class "Default")
      (node (ref "IC1") (pin "7") (pinfunction "DQ3_7") (pintype "tri_state"))
      (node (ref "U1") (pin "109") (pinfunction "D3_109") (pintype "bidirectional"))
    )
    (net (code "131") (name "DATA4") (class "Default")
      (node (ref "IC1") (pin "8") (pinfunction "DQ4_8") (pintype "tri_state"))
      (node (ref "U1") (pin "110") (pinfunction "D4_110") (pintype "bidirectional"))
    )
    (net (code "132") (name "DATA5") (class "Default")
      (node (ref "IC1") (pin "10") (pinfunction "DQ5_10") (pintype "tri_state"))
      (node (ref "U1") (pin "111") (pinfunction "D5_111") (pintype "bidirectional"))
    )
    (net (code "133") (name "DATA6") (class "Default")
      (node (ref "IC1") (pin "11") (pinfunction "DQ6_11") (pintype "tri_state"))
      (node (ref "U1") (pin "112") (pinfunction "D6_112") (pintype "bidirectional"))
    )
    (net (code "134") (name "DATA7") (class "Default")
      (node (ref "IC1") (pin "13") (pinfunction "DQ7_13") (pintype "tri_state"))
      (node (ref "U1") (pin "118") (pinfunction "D7_118") (pintype "bidirectional"))
    )
    (net (code "135") (name "DATA8") (class "Default")
      (node (ref "IC1") (pin "42") (pinfunction "DQ8_42") (pintype "tri_state"))
      (node (ref "U1") (pin "119") (pinfunction "D8_119") (pintype "bidirectional"))
    )
    (net (code "136") (name "DATA9") (class "Default")
      (node (ref "IC1") (pin "44") (pinfunction "DQ9_44") (pintype "tri_state"))
      (node (ref "U1") (pin "120") (pinfunction "D9_120") (pintype "bidirectional"))
    )
    (net (code "137") (name "DATA10") (class "Default")
      (node (ref "IC1") (pin "45") (pinfunction "DQ10_45") (pintype "tri_state"))
      (node (ref "U1") (pin "121") (pinfunction "D10_121") (pintype "bidirectional"))
    )
    (net (code "138") (name "DATA11") (class "Default")
      (node (ref "IC1") (pin "47") (pinfunction "DQ11_47") (pintype "tri_state"))
      (node (ref "U1") (pin "122") (pinfunction "D11_122") (pintype "bidirectional"))
    )
    (net (code "139") (name "DATA12") (class "Default")
      (node (ref "IC1") (pin "48") (pinfunction "DQ12_48") (pintype "tri_state"))
      (node (ref "U1") (pin "123") (pinfunction "D12_123") (pintype "bidirectional"))
    )
    (net (code "140") (name "DATA13") (class "Default")
      (node (ref "IC1") (pin "50") (pinfunction "DQ13_50") (pintype "tri_state"))
      (node (ref "U1") (pin "124") (pinfunction "D13_124") (pintype "bidirectional"))
    )
    (net (code "141") (name "DATA14") (class "Default")
      (node (ref "IC1") (pin "51") (pinfunction "DQ14_51") (pintype "tri_state"))
      (node (ref "U1") (pin "125") (pinfunction "D14_125") (pintype "bidirectional"))
    )
    (net (code "142") (name "DATA15") (class "Default")
      (node (ref "IC1") (pin "53") (pinfunction "DQ15_53") (pintype "tri_state"))
      (node (ref "U1") (pin "126") (pinfunction "D15_126") (pintype "bidirectional"))
    )
    (net (code "143") (name "DATA16") (class "Default")
      (node (ref "IC2") (pin "2") (pinfunction "DQ0_2") (pintype "tri_state"))
      (node (ref "U1") (pin "128") (pinfunction "PC16_128") (pintype "bidirectional"))
    )
    (net (code "144") (name "DATA17") (class "Default")
      (node (ref "IC2") (pin "4") (pinfunction "DQ1_4") (pintype "tri_state"))
      (node (ref "U1") (pin "129") (pinfunction "PC17_129") (pintype "bidirectional"))
    )
    (net (code "145") (name "DATA18") (class "Default")
      (node (ref "IC2") (pin "5") (pinfunction "DQ2_5") (pintype "tri_state"))
      (node (ref "U1") (pin "130") (pinfunction "PC18_130") (pintype "bidirectional"))
    )
    (net (code "146") (name "DATA19") (class "Default")
      (node (ref "IC2") (pin "7") (pinfunction "DQ3_7") (pintype "tri_state"))
      (node (ref "U1") (pin "131") (pinfunction "PC19_131") (pintype "bidirectional"))
    )
    (net (code "147") (name "DATA20") (class "Default")
      (node (ref "IC2") (pin "8") (pinfunction "DQ4_8") (pintype "tri_state"))
      (node (ref "U1") (pin "134") (pinfunction "PC20_134") (pintype "bidirectional"))
    )
    (net (code "148") (name "DATA21") (class "Default")
      (node (ref "IC2") (pin "10") (pinfunction "DQ5_10") (pintype "tri_state"))
      (node (ref "U1") (pin "135") (pinfunction "PC21_135") (pintype "bidirectional"))
    )
    (net (code "149") (name "DATA22") (class "Default")
      (node (ref "IC2") (pin "11") (pinfunction "DQ6_11") (pintype "tri_state"))
      (node (ref "U1") (pin "136") (pinfunction "PC22_136") (pintype "bidirectional"))
    )
    (net (code "150") (name "DATA23") (class "Default")
      (node (ref "IC2") (pin "13") (pinfunction "DQ7_13") (pintype "tri_state"))
      (node (ref "U1") (pin "137") (pinfunction "PC23_137") (pintype "bidirectional"))
    )
    (net (code "151") (name "DATA24") (class "Default")
      (node (ref "IC2") (pin "42") (pinfunction "DQ8_42") (pintype "tri_state"))
      (node (ref "U1") (pin "138") (pinfunction "PC24_138") (pintype "bidirectional"))
    )
    (net (code "152") (name "DATA25") (class "Default")
      (node (ref "IC2") (pin "44") (pinfunction "DQ9_44") (pintype "tri_state"))
      (node (ref "U1") (pin "139") (pinfunction "PC25_139") (pintype "bidirectional"))
    )
    (net (code "153") (name "DATA26") (class "Default")
      (node (ref "IC2") (pin "45") (pinfunction "DQ10_45") (pintype "tri_state"))
      (node (ref "U1") (pin "140") (pinfunction "PC26_140") (pintype "bidirectional"))
    )
    (net (code "154") (name "DATA27") (class "Default")
      (node (ref "IC2") (pin "47") (pinfunction "DQ11_47") (pintype "tri_state"))
      (node (ref "U1") (pin "141") (pinfunction "PC27_141") (pintype "bidirectional"))
    )
    (net (code "155") (name "DATA28") (class "Default")
      (node (ref "IC2") (pin "48") (pinfunction "DQ12_48") (pintype "tri_state"))
      (node (ref "U1") (pin "142") (pinfunction "PC28_142") (pintype "bidirectional"))
    )
    (net (code "156") (name "DATA29") (class "Default")
      (node (ref "IC2") (pin "50") (pinfunction "DQ13_50") (pintype "tri_state"))
      (node (ref "U1") (pin "143") (pinfunction "PC29_143") (pintype "bidirectional"))
    )
    (net (code "157") (name "DATA30") (class "Default")
      (node (ref "IC2") (pin "51") (pinfunction "DQ14_51") (pintype "tri_state"))
      (node (ref "U1") (pin "144") (pinfunction "PC30_144") (pintype "bidirectional"))
    )
    (net (code "158") (name "DATA31") (class "Default")
      (node (ref "IC2") (pin "53") (pinfunction "DQ15_53") (pintype "tri_state"))
      (node (ref "U1") (pin "145") (pinfunction "PC31_145") (pintype "bidirectional"))
    )
    (net (code "174") (name "FIQ") (class "Default")
      (node (ref "SV1") (pin "19") (pinfunction "19_19") (pintype "passive"))
      (node (ref "U1") (pin "56") (pinfunction "PC13_56") (pintype "bidirectional"))
    )
    (net (code "175") (name "GND") (class "Default")
      (node (ref "C1") (pin "2") (pinfunction "2_2") (pintype "passive"))
      (node (ref "C10") (pin "2") (pinfunction "2_2") (pintype "passive"))
      (node (ref "C11") (pin "2") (pinfunction "2_2") (pintype "passive"))
      (node (ref "C12") (pin "2") (pinfunction "2_2") (pintype "passive"))
      (node (ref "C13") (pin "2") (pinfunction "2_2") (pintype "passive"))
      (node (ref "C14") (pin "2") (pinfunction "2_2") (pintype "passive"))
      (node (ref "C15") (pin "2") (pinfunction "2_2") (pintype "passive"))
      (node (ref "C16") (pin "2") (pinfunction "2_2") (pintype "passive"))
      (node (ref "C17") (pin "2") (pinfunction "2_2") (pintype "passive"))
      (node (ref "C18") (pin "2") (pinfunction "2_2") (pintype "passive"))
      (node (ref "C2") (pin "2") (pinfunction "2_2") (pintype "passive"))
      (node (ref "C20") (pin "2") (pinfunction "2_2") (pintype "passive"))
      (node (ref "C21") (pin "2") (pinfunction "2_2") (pintype "passive"))
      (node (ref "C22") (pin "2") (pinfunction "2_2") (pintype "passive"))
      (node (ref "C25") (pin "2") (pinfunction "2_2") (pintype "passive"))
      (node (ref "C26") (pin "2") (pinfunction "2_2") (pintype "passive"))
      (node (ref "C27") (pin "2") (pinfunction "2_2") (pintype "passive"))
      (node (ref "C28") (pin "2") (pinfunction "2_2") (pintype "passive"))
      (node (ref "C29") (pin "2") (pinfunction "2_2") (pintype "passive"))
      (node (ref "C3") (pin "2") (pinfunction "2_2") (pintype "passive"))
      (node (ref "C30") (pin "2") (pinfunction "2_2") (pintype "passive"))
      (node (ref "C31") (pin "2") (pinfunction "2_2") (pintype "passive"))
      (node (ref "C32") (pin "2") (pinfunction "2_2") (pintype "passive"))
      (node (ref "C33") (pin "2") (pinfunction "2_2") (pintype "passive"))
      (node (ref "C34") (pin "2") (pinfunction "2_2") (pintype "passive"))
      (node (ref "C35") (pin "2") (pinfunction "2_2") (pintype "passive"))
      (node (ref "C36") (pin "2") (pinfunction "2_2") (pintype "passive"))
      (node (ref "C37") (pin "2") (pinfunction "2_2") (pintype "passive"))
      (node (ref "C38") (pin "2") (pinfunction "2_2") (pintype "passive"))
      (node (ref "C39") (pin "2") (pinfunction "2_2") (pintype "passive"))
      (node (ref "C4") (pin "2") (pinfunction "2_2") (pintype "passive"))
      (node (ref "C40") (pin "2") (pinfunction "2_2") (pintype "passive"))
      (node (ref "C41") (pin "2") (pinfunction "2_2") (pintype "passive"))
      (node (ref "C42") (pin "2") (pinfunction "2_2") (pintype "passive"))
      (node (ref "C43") (pin "2") (pinfunction "2_2") (pintype "passive"))
      (node (ref "C45") (pin "2") (pinfunction "2_2") (pintype "passive"))
      (node (ref "C46") (pin "2") (pinfunction "2_2") (pintype "passive"))
      (node (ref "C47") (pin "2") (pinfunction "2_2") (pintype "passive"))
      (node (ref "C48") (pin "2") (pinfunction "2_2") (pintype "passive"))
      (node (ref "C49") (pin "2") (pinfunction "2_2") (pintype "passive"))
      (node (ref "C5") (pin "2") (pinfunction "2_2") (pintype "passive"))
      (node (ref "C51") (pin "2") (pinfunction "2_2") (pintype "passive"))
      (node (ref "C52") (pin "2") (pinfunction "2_2") (pintype "passive"))
      (node (ref "C53") (pin "2") (pinfunction "2_2") (pintype "passive"))
      (node (ref "C54") (pin "2") (pinfunction "2_2") (pintype "passive"))
      (node (ref "C55") (pin "2") (pinfunction "2_2") (pintype "passive"))
      (node (ref "C58") (pin "2") (pinfunction "2_2") (pintype "passive"))
      (node (ref "C59") (pin "2") (pinfunction "2_2") (pintype "passive"))
      (node (ref "C6") (pin "2") (pinfunction "2_2") (pintype "passive"))
      (node (ref "C60") (pin "2") (pinfunction "2_2") (pintype "passive"))
      (node (ref "C61") (pin "2") (pinfunction "2_2") (pintype "passive"))
      (node (ref "C62") (pin "2") (pinfunction "2_2") (pintype "passive"))
      (node (ref "C63") (pin "2") (pinfunction "2_2") (pintype "passive"))
      (node (ref "C7") (pin "2") (pinfunction "2_2") (pintype "passive"))
      (node (ref "C8") (pin "2") (pinfunction "2_2") (pintype "passive"))
      (node (ref "C9") (pin "2") (pinfunction "2_2") (pintype "passive"))
      (node (ref "CON1") (pin "5") (pinfunction "GND_5") (pintype "bidirectional"))
      (node (ref "CON1") (pin "SH1") (pinfunction "GND_SH1") (pintype "bidirectional"))
      (node (ref "CON1") (pin "SH2") (pinfunction "GND_SH2") (pintype "bidirectional"))
      (node (ref "CON1") (pin "SH3") (pinfunction "GND_SH3") (pintype "bidirectional"))
      (node (ref "CON1") (pin "SH4") (pinfunction "GND_SH4") (pintype "bidirectional"))
      (node (ref "CON1") (pin "SH5") (pinfunction "GND_SH5") (pintype "bidirectional"))
      (node (ref "CON1") (pin "SH6") (pinfunction "GND_SH6") (pintype "bidirectional"))
      (node (ref "CON1") (pin "SH7") (pinfunction "GND_SH7") (pintype "bidirectional"))
      (node (ref "CON1") (pin "SH8") (pinfunction "GND_SH8") (pintype "bidirectional"))
      (node (ref "CON2") (pin "GND1") (pinfunction "GND_GND1") (pintype "power_in"))
      (node (ref "CON2") (pin "GND2") (pinfunction "GND_GND2") (pintype "power_in"))
      (node (ref "CON2") (pin "GND3") (pinfunction "GND_GND3") (pintype "power_in"))
      (node (ref "CON2") (pin "GND4") (pinfunction "GND_GND4") (pintype "power_in"))
      (node (ref "CON2") (pin "P$6") (pinfunction "VSS_P$6") (pintype "bidirectional"))
      (node (ref "GND") (pin "TP") (pinfunction "TP_TP") (pintype "input"))
      (node (ref "GND15") (pin "TP") (pinfunction "TP_TP") (pintype "input"))
      (node (ref "GND99") (pin "TP") (pinfunction "TP_TP") (pintype "input"))
      (node (ref "IC1") (pin "12") (pinfunction "VSSQ_12") (pintype "power_in"))
      (node (ref "IC1") (pin "28") (pinfunction "VSS_28") (pintype "power_in"))
      (node (ref "IC1") (pin "41") (pinfunction "VSS_41") (pintype "power_in"))
      (node (ref "IC1") (pin "46") (pinfunction "VSSQ_46") (pintype "power_in"))
      (node (ref "IC1") (pin "52") (pinfunction "VSSQ_52") (pintype "power_in"))
      (node (ref "IC1") (pin "54") (pinfunction "VSS_54") (pintype "power_in"))
      (node (ref "IC1") (pin "6") (pinfunction "VSSQ_6") (pintype "power_in"))
      (node (ref "IC2") (pin "12") (pinfunction "VSSQ_12") (pintype "power_in"))
      (node (ref "IC2") (pin "28") (pinfunction "VSS_28") (pintype "power_in"))
      (node (ref "IC2") (pin "41") (pinfunction "VSS_41") (pintype "power_in"))
      (node (ref "IC2") (pin "46") (pinfunction "VSSQ_46") (pintype "power_in"))
      (node (ref "IC2") (pin "52") (pinfunction "VSSQ_52") (pintype "power_in"))
      (node (ref "IC2") (pin "54") (pinfunction "VSS_54") (pintype "power_in"))
      (node (ref "IC2") (pin "6") (pinfunction "VSSQ_6") (pintype "power_in"))
      (node (ref "IC4") (pin "3") (pinfunction "3_3") (pintype "bidirectional"))
      (node (ref "IC4") (pin "5") (pinfunction "GND_5") (pintype "bidirectional"))
      (node (ref "IC5") (pin "1") (pinfunction "GND_1") (pintype "bidirectional"))
      (node (ref "IC6") (pin "7") (pinfunction "GND_7") (pintype "power_in"))
      (node (ref "IC7") (pin "1") (pinfunction "GND_1") (pintype "bidirectional"))
      (node (ref "R11") (pin "1") (pinfunction "1_1") (pintype "passive"))
      (node (ref "R12") (pin "1") (pinfunction "1_1") (pintype "passive"))
      (node (ref "R17") (pin "2") (pinfunction "2_2") (pintype "passive"))
      (node (ref "R19") (pin "2") (pinfunction "2_2") (pintype "passive"))
      (node (ref "R36") (pin "1") (pinfunction "1_1") (pintype "passive"))
      (node (ref "R38") (pin "1") (pinfunction "1_1") (pintype "passive"))
      (node (ref "SV1") (pin "1") (pinfunction "1_1") (pintype "passive"))
      (node (ref "SV1") (pin "14") (pinfunction "14_14") (pintype "passive"))
      (node (ref "SV1") (pin "23") (pinfunction "23_23") (pintype "passive"))
      (node (ref "SV1") (pin "36") (pinfunction "36_36") (pintype "passive"))
      (node (ref "TP3") (pin "TP") (pinfunction "TP_TP") (pintype "input"))
      (node (ref "TP5") (pin "TP") (pinfunction "TP_TP") (pintype "input"))
      (node (ref "U1") (pin "113") (pinfunction "GND_113") (pintype "bidirectional"))
      (node (ref "U1") (pin "133") (pinfunction "GND_133") (pintype "bidirectional"))
      (node (ref "U1") (pin "14") (pinfunction "GND_14") (pintype "bidirectional"))
      (node (ref "U1") (pin "146") (pinfunction "GND_146") (pintype "bidirectional"))
      (node (ref "U1") (pin "151") (pinfunction "GNDPLL_151") (pintype "bidirectional"))
      (node (ref "U1") (pin "153") (pinfunction "GNDPLL_153") (pintype "bidirectional"))
      (node (ref "U1") (pin "156") (pinfunction "GNDANA_156") (pintype "bidirectional"))
      (node (ref "U1") (pin "170") (pinfunction "GND_170") (pintype "bidirectional"))
      (node (ref "U1") (pin "173") (pinfunction "GND_173") (pintype "bidirectional"))
      (node (ref "U1") (pin "188") (pinfunction "GND_188") (pintype "bidirectional"))
      (node (ref "U1") (pin "200") (pinfunction "GND_200") (pintype "bidirectional"))
      (node (ref "U1") (pin "204") (pinfunction "GND_204") (pintype "bidirectional"))
      (node (ref "U1") (pin "25") (pinfunction "GND_25") (pintype "bidirectional"))
      (node (ref "U1") (pin "33") (pinfunction "GND_33") (pintype "bidirectional"))
      (node (ref "U1") (pin "39") (pinfunction "GND_39") (pintype "bidirectional"))
      (node (ref "U1") (pin "42") (pinfunction "TST_42") (pintype "bidirectional"))
      (node (ref "U1") (pin "43") (pinfunction "JTAGSEL_43") (pintype "bidirectional"))
      (node (ref "U1") (pin "44") (pinfunction "GNDBU_44") (pintype "bidirectional"))
      (node (ref "U1") (pin "53") (pinfunction "GND_53") (pintype "bidirectional"))
      (node (ref "U1") (pin "6") (pinfunction "GND_6") (pintype "bidirectional"))
      (node (ref "U1") (pin "66") (pinfunction "GND_66") (pintype "bidirectional"))
      (node (ref "U1") (pin "78") (pinfunction "GND_78") (pintype "bidirectional"))
      (node (ref "U1") (pin "91") (pinfunction "GND_91") (pintype "bidirectional"))
      (node (ref "USB") (pin "1") (pinfunction "1_1") (pintype "passive"))
      (node (ref "X1") (pin "1") (pinfunction "1_1") (pintype "passive"))
      (node (ref "X2") (pin "1") (pinfunction "1_1") (pintype "passive"))
    )
    (net (code "176") (name "GPIO3") (class "Default")
      (node (ref "SV1") (pin "24") (pinfunction "24_24") (pintype "passive"))
      (node (ref "U1") (pin "184") (pinfunction "PA5_184") (pintype "bidirectional"))
    )
    (net (code "177") (name "GPIO31") (class "Default")
      (node (ref "SV1") (pin "31") (pinfunction "31_31") (pintype "passive"))
      (node (ref "U1") (pin "164") (pinfunction "PB21_164") (pintype "bidirectional"))
    )
    (net (code "178") (name "GPIO32") (class "Default")
      (node (ref "SV1") (pin "32") (pinfunction "32_32") (pintype "passive"))
      (node (ref "U1") (pin "163") (pinfunction "PB20_163") (pintype "bidirectional"))
    )
    (net (code "179") (name "GPIO33") (class "Default")
      (node (ref "SV1") (pin "33") (pinfunction "33_33") (pintype "passive"))
      (node (ref "U1") (pin "162") (pinfunction "PB11_162") (pintype "bidirectional"))
    )
    (net (code "180") (name "GPIO34") (class "Default")
      (node (ref "SV1") (pin "34") (pinfunction "34_34") (pintype "passive"))
      (node (ref "U1") (pin "161") (pinfunction "PB10_161") (pintype "bidirectional"))
    )
    (net (code "181") (name "GPIO35") (class "Default")
      (node (ref "SV1") (pin "35") (pinfunction "35_35") (pintype "passive"))
      (node (ref "U1") (pin "159") (pinfunction "PC1_159") (pintype "bidirectional"))
    )
    (net (code "182") (name "GPIO36") (class "Default")
      (node (ref "U1") (pin "158") (pinfunction "PC0_158") (pintype "bidirectional"))
    )
    (net (code "183") (name "HDMA") (class "Default")
      (node (ref "R10") (pin "1") (pinfunction "1_1") (pintype "passive"))
      (node (ref "U1") (pin "50") (pinfunction "HDMA_50") (pintype "bidirectional"))
    )
    (net (code "184") (name "HDPA") (class "Default")
      (node (ref "R9") (pin "1") (pinfunction "1_1") (pintype "passive"))
      (node (ref "U1") (pin "51") (pinfunction "HDPA_51") (pintype "bidirectional"))
    )
    (net (code "185") (name "HSE_IN") (class "Default")
      (node (ref "C25") (pin "1") (pinfunction "1_1") (pintype "passive"))
      (node (ref "Q1") (pin "1") (pinfunction "1_1") (pintype "passive"))
      (node (ref "U1") (pin "149") (pinfunction "XIN_149") (pintype "bidirectional"))
    )
    (net (code "186") (name "HSE_OUT") (class "Default")
      (node (ref "C26") (pin "1") (pinfunction "1_1") (pintype "passive"))
      (node (ref "Q1") (pin "3") (pinfunction "2_3") (pintype "passive"))
      (node (ref "U1") (pin "150") (pinfunction "XOUT_150") (pintype "bidirectional"))
    )
    (net (code "187") (name "I2C_SCL") (class "Default")
      (node (ref "R29") (pin "1") (pinfunction "1_1") (pintype "passive"))
      (node (ref "SV1") (pin "17") (pinfunction "17_17") (pintype "passive"))
      (node (ref "U1") (pin "1") (pinfunction "PA24_1") (pintype "bidirectional"))
    )
    (net (code "188") (name "I2C_SDA") (class "Default")
      (node (ref "R28") (pin "1") (pinfunction "1_1") (pintype "passive"))
      (node (ref "SV1") (pin "18") (pinfunction "18_18") (pintype "passive"))
      (node (ref "U1") (pin "208") (pinfunction "PA23_208") (pintype "bidirectional"))
    )
    (net (code "189") (name "IRQ1") (class "Default")
      (node (ref "SV1") (pin "20") (pinfunction "20_20") (pintype "passive"))
      (node (ref "U1") (pin "127") (pinfunction "PC15_127") (pintype "bidirectional"))
    )
    (net (code "190") (name "LED_BLUE") (class "Default")
      (node (ref "R20") (pin "1") (pinfunction "1_1") (pintype "passive"))
      (node (ref "U1") (pin "60") (pinfunction "PC9_60") (pintype "bidirectional"))
    )
    (net (code "191") (name "LED_GREEN") (class "Default")
      (node (ref "R21") (pin "1") (pinfunction "1_1") (pintype "passive"))
      (node (ref "U1") (pin "64") (pinfunction "PC7_64") (pintype "bidirectional"))
    )
    (net (code "192") (name "LED_RED") (class "Default")
      (node (ref "R22") (pin "1") (pinfunction "1_1") (pintype "passive"))
      (node (ref "U1") (pin "63") (pinfunction "PC6_63") (pintype "bidirectional"))
    )
    (net (code "193") (name "LSE_IN") (class "Default")
      (node (ref "C27") (pin "1") (pinfunction "1_1") (pintype "passive"))
      (node (ref "Q2") (pin "1") (pinfunction "1_1") (pintype "passive"))
      (node (ref "U1") (pin "46") (pinfunction "XIN32_46") (pintype "bidirectional"))
    )
    (net (code "194") (name "LSE_OUT") (class "Default")
      (node (ref "C28") (pin "1") (pinfunction "1_1") (pintype "passive"))
      (node (ref "Q2") (pin "2") (pinfunction "2_2") (pintype "passive"))
      (node (ref "U1") (pin "45") (pinfunction "XOUT32_45") (pintype "bidirectional"))
    )
    (net (code "195") (name "MCCDA") (class "Default")
      (node (ref "CON2") (pin "P$3") (pinfunction "CMD_P$3") (pintype "input"))
      (node (ref "R35") (pin "1") (pinfunction "1_1") (pintype "passive"))
      (node (ref "U1") (pin "186") (pinfunction "PA7_186") (pintype "bidirectional"))
    )
    (net (code "197") (name "MCCDT") (class "Default")
      (node (ref "CON2") (pin "P$13") (pinfunction "CD_P$13") (pintype "power_in"))
      (node (ref "R23") (pin "2") (pinfunction "2_2") (pintype "passive"))
      (node (ref "U1") (pin "28") (pinfunction "PB19_28") (pintype "bidirectional"))
    )
    (net (code "198") (name "MCCK") (class "Default")
      (node (ref "CON2") (pin "P$5") (pinfunction "CLK_P$5") (pintype "bidirectional"))
      (node (ref "U1") (pin "189") (pinfunction "PA8_189") (pintype "bidirectional"))
    )
    (net (code "199") (name "MCDA0") (class "Default")
      (node (ref "CON2") (pin "P$7") (pinfunction "DAT0_P$7") (pintype "power_in"))
      (node (ref "R8") (pin "2") (pinfunction "2_2") (pintype "passive"))
      (node (ref "U1") (pin "185") (pinfunction "PA6_185") (pintype "bidirectional"))
    )
    (net (code "200") (name "MCDA1") (class "Default")
      (node (ref "CON2") (pin "P$8") (pinfunction "DAT1_P$8") (pintype "power_in"))
      (node (ref "R7") (pin "2") (pinfunction "2_2") (pintype "passive"))
      (node (ref "U1") (pin "190") (pinfunction "PA9_190") (pintype "bidirectional"))
    )
    (net (code "201") (name "MCDA2") (class "Default")
      (node (ref "CON2") (pin "P$1") (pinfunction "DAT2_P$1") (pintype "output"))
      (node (ref "R32") (pin "2") (pinfunction "2_2") (pintype "passive"))
      (node (ref "U1") (pin "191") (pinfunction "PA10_191") (pintype "bidirectional"))
    )
    (net (code "202") (name "MCDA3") (class "Default")
      (node (ref "CON2") (pin "P$2") (pinfunction "CD/DAT3_P$2") (pintype "input"))
      (node (ref "R31") (pin "2") (pinfunction "2_2") (pintype "passive"))
      (node (ref "U1") (pin "192") (pinfunction "PA11_192") (pintype "bidirectional"))
    )
    (net (code "207") (name "MII_ECOL") (class "Default")
      (node (ref "U1") (pin "8") (pinfunction "PA29_8") (pintype "bidirectional"))
    )
    (net (code "208") (name "MII_ECRS") (class "Default")
      (node (ref "U1") (pin "7") (pinfunction "PA28_7") (pintype "bidirectional"))
    )
    (net (code "209") (name "MII_ECRSDV") (class "Default")
      (node (ref "U1") (pin "198") (pinfunction "PA17_198") (pintype "bidirectional"))
      (node (ref "X1") (pin "6") (pinfunction "6_6") (pintype "passive"))
    )
    (net (code "210") (name "MII_EMDC") (class "Default")
      (node (ref "U1") (pin "205") (pinfunction "PA20_205") (pintype "bidirectional"))
      (node (ref "X2") (pin "8") (pinfunction "8_8") (pintype "passive"))
    )
    (net (code "211") (name "MII_EMDIO") (class "Default")
      (node (ref "U1") (pin "206") (pinfunction "PA21_206") (pintype "bidirectional"))
      (node (ref "X1") (pin "8") (pinfunction "8_8") (pintype "passive"))
    )
    (net (code "212") (name "MII_ERX0") (class "Default")
      (node (ref "U1") (pin "195") (pinfunction "PA14_195") (pintype "bidirectional"))
      (node (ref "X1") (pin "4") (pinfunction "4_4") (pintype "passive"))
    )
    (net (code "213") (name "MII_ERX1") (class "Default")
      (node (ref "U1") (pin "196") (pinfunction "PA15_196") (pintype "bidirectional"))
      (node (ref "X1") (pin "3") (pinfunction "3_3") (pintype "passive"))
    )
    (net (code "214") (name "MII_ERXCK") (class "Default")
      (node (ref "U1") (pin "4") (pinfunction "PA27_4") (pintype "bidirectional"))
    )
    (net (code "215") (name "MII_ERXER") (class "Default")
      (node (ref "U1") (pin "201") (pinfunction "PA18_201") (pintype "bidirectional"))
      (node (ref "X1") (pin "5") (pinfunction "5_5") (pintype "passive"))
    )
    (net (code "216") (name "MII_ETX0") (class "Default")
      (node (ref "U1") (pin "193") (pinfunction "PA12_193") (pintype "bidirectional"))
      (node (ref "X2") (pin "4") (pinfunction "4_4") (pintype "passive"))
    )
    (net (code "217") (name "MII_ETX1") (class "Default")
      (node (ref "U1") (pin "194") (pinfunction "PA13_194") (pintype "bidirectional"))
      (node (ref "X2") (pin "3") (pinfunction "3_3") (pintype "passive"))
    )
    (net (code "218") (name "MII_ETXCK") (class "Default")
      (node (ref "U1") (pin "202") (pinfunction "PA19_202") (pintype "bidirectional"))
      (node (ref "X2") (pin "2") (pinfunction "2_2") (pintype "passive"))
    )
    (net (code "219") (name "MII_ETXEN") (class "Default")
      (node (ref "U1") (pin "197") (pinfunction "PA16_197") (pintype "bidirectional"))
      (node (ref "X2") (pin "5") (pinfunction "5_5") (pintype "passive"))
    )
    (net (code "220") (name "MII_INT") (class "Default")
      (node (ref "R3") (pin "1") (pinfunction "1_1") (pintype "passive"))
      (node (ref "U1") (pin "59") (pinfunction "PC14_59") (pintype "bidirectional"))
      (node (ref "X1") (pin "7") (pinfunction "7_7") (pintype "passive"))
    )
    (net (code "221") (name "MII_RST") (class "Default")
      (node (ref "U1") (pin "16") (pinfunction "PB5_16") (pintype "bidirectional"))
      (node (ref "X2") (pin "7") (pinfunction "7_7") (pintype "passive"))
    )
    (net (code "222") (name "Net-(C21-Pad1)") (class "Default")
      (node (ref "C21") (pin "1") (pinfunction "1_1") (pintype "passive"))
      (node (ref "R1") (pin "1") (pinfunction "1_1") (pintype "passive"))
    )
    (net (code "223") (name "Net-(CON1-VCC)") (class "Default")
      (node (ref "CON1") (pin "1") (pinfunction "VCC_1") (pintype "bidirectional"))
      (node (ref "F1") (pin "1") (pinfunction "1_1") (pintype "passive"))
    )
    (net (code "224") (name "Net-(IC4-Pad4)") (class "Default")
      (node (ref "IC4") (pin "4") (pinfunction "4_4") (pintype "bidirectional"))
      (node (ref "R36") (pin "2") (pinfunction "2_2") (pintype "passive"))
    )
    (net (code "225") (name "Net-(IC5-BST)") (class "Default")
      (node (ref "C56") (pin "1") (pinfunction "1_1") (pintype "passive"))
      (node (ref "IC5") (pin "6") (pinfunction "BST_6") (pintype "bidirectional"))
    )
    (net (code "226") (name "Net-(IC5-FB)") (class "Default")
      (node (ref "IC5") (pin "4") (pinfunction "FB_4") (pintype "bidirectional"))
      (node (ref "R13") (pin "1") (pinfunction "1_1") (pintype "passive"))
    )
    (net (code "227") (name "Net-(IC5-SW)") (class "Default")
      (node (ref "C56") (pin "2") (pinfunction "2_2") (pintype "passive"))
      (node (ref "IC5") (pin "2") (pinfunction "SW_2") (pintype "bidirectional"))
      (node (ref "L1") (pin "1") (pinfunction "1_1") (pintype "passive"))
    )
    (net (code "228") (name "Net-(IC6-{slash}WP)") (class "Default")
      (node (ref "IC6") (pin "5") (pinfunction "/WP_5") (pintype "input"))
      (node (ref "R30") (pin "1") (pinfunction "1_1") (pintype "passive"))
    )
    (net (code "229") (name "Net-(IC7-BST)") (class "Default")
      (node (ref "C57") (pin "1") (pinfunction "1_1") (pintype "passive"))
      (node (ref "IC7") (pin "6") (pinfunction "BST_6") (pintype "bidirectional"))
    )
    (net (code "230") (name "Net-(IC7-FB)") (class "Default")
      (node (ref "IC7") (pin "4") (pinfunction "FB_4") (pintype "bidirectional"))
      (node (ref "R15") (pin "1") (pinfunction "1_1") (pintype "passive"))
    )
    (net (code "231") (name "Net-(IC7-SW)") (class "Default")
      (node (ref "C57") (pin "2") (pinfunction "2_2") (pintype "passive"))
      (node (ref "IC7") (pin "2") (pinfunction "SW_2") (pintype "bidirectional"))
      (node (ref "L2") (pin "1") (pinfunction "1_1") (pintype "passive"))
    )
    (net (code "232") (name "Net-(LED1-Pad1)") (class "Default")
      (node (ref "LED1") (pin "1") (pinfunction "1_1") (pintype "passive"))
      (node (ref "R20") (pin "2") (pinfunction "2_2") (pintype "passive"))
    )
    (net (code "233") (name "Net-(LED1-Pad3)") (class "Default")
      (node (ref "LED1") (pin "3") (pinfunction "3_3") (pintype "passive"))
      (node (ref "R22") (pin "2") (pinfunction "2_2") (pintype "passive"))
    )
    (net (code "234") (name "Net-(LED1-Pad4)") (class "Default")
      (node (ref "LED1") (pin "4") (pinfunction "4_4") (pintype "passive"))
      (node (ref "R21") (pin "2") (pinfunction "2_2") (pintype "passive"))
    )
    (net (code "235") (name "Net-(R13-Pad2)") (class "Default")
      (node (ref "R13") (pin "2") (pinfunction "2_2") (pintype "passive"))
      (node (ref "R16") (pin "1") (pinfunction "1_1") (pintype "passive"))
      (node (ref "R17") (pin "1") (pinfunction "1_1") (pintype "passive"))
    )
    (net (code "236") (name "Net-(R15-Pad2)") (class "Default")
      (node (ref "R15") (pin "2") (pinfunction "2_2") (pintype "passive"))
      (node (ref "R18") (pin "1") (pinfunction "1_1") (pintype "passive"))
      (node (ref "R19") (pin "1") (pinfunction "1_1") (pintype "passive"))
    )
    (net (code "237") (name "Net-(U1E-ADVREF)") (class "Default")
      (node (ref "L3") (pin "2") (pinfunction "2_2") (pintype "passive"))
      (node (ref "U1") (pin "157") (pinfunction "ADVREF_157") (pintype "bidirectional"))
      (node (ref "U1") (pin "160") (pinfunction "VDDANA_160") (pintype "bidirectional"))
    )
    (net (code "238") (name "PLLRCA") (class "Default")
      (node (ref "C22") (pin "1") (pinfunction "1_1") (pintype "passive"))
      (node (ref "R1") (pin "2") (pinfunction "2_2") (pintype "passive"))
      (node (ref "U1") (pin "154") (pinfunction "PLLRCA_154") (pintype "bidirectional"))
    )
    (net (code "239") (name "RAS") (class "Default")
      (node (ref "IC1") (pin "18") (pinfunction "~{RAS}_18") (pintype "input"))
      (node (ref "IC2") (pin "18") (pinfunction "~{RAS}_18") (pintype "input"))
      (node (ref "U1") (pin "105") (pinfunction "RAS_105") (pintype "bidirectional"))
    )
    (net (code "240") (name "RECOVERY") (class "Default")
      (node (ref "+1V1") (pin "TP") (pinfunction "TP_TP") (pintype "input"))
      (node (ref "U1") (pin "3") (pinfunction "PA26_3") (pintype "bidirectional"))
    )
    (net (code "241") (name "SDA10") (class "Default")
      (node (ref "IC1") (pin "22") (pinfunction "A10_22") (pintype "input"))
      (node (ref "IC2") (pin "22") (pinfunction "A10_22") (pintype "input"))
      (node (ref "U1") (pin "100") (pinfunction "SDA10_100") (pintype "bidirectional"))
    )
    (net (code "242") (name "SDCK") (class "Default")
      (node (ref "IC1") (pin "38") (pinfunction "CLK_38") (pintype "input"))
      (node (ref "IC2") (pin "38") (pinfunction "CLK_38") (pintype "input"))
      (node (ref "U1") (pin "115") (pinfunction "SDCK_115") (pintype "bidirectional"))
    )
    (net (code "243") (name "SDCKE") (class "Default")
      (node (ref "IC1") (pin "37") (pinfunction "CKE_37") (pintype "input"))
      (node (ref "IC2") (pin "37") (pinfunction "CKE_37") (pintype "input"))
      (node (ref "U1") (pin "117") (pinfunction "SDCKE_117") (pintype "bidirectional"))
    )
    (net (code "244") (name "SDCS") (class "Default")
      (node (ref "IC1") (pin "19") (pinfunction "\\CS_19") (pintype "input"))
      (node (ref "IC2") (pin "19") (pinfunction "\\CS_19") (pintype "input"))
      (node (ref "R2") (pin "1") (pinfunction "1_1") (pintype "passive"))
      (node (ref "U1") (pin "103") (pinfunction "SDCS/NCS1_103") (pintype "bidirectional"))
    )
    (net (code "245") (name "SDWE") (class "Default")
      (node (ref "IC1") (pin "16") (pinfunction "~{WE}_16") (pintype "input"))
      (node (ref "IC2") (pin "16") (pinfunction "~{WE}_16") (pintype "input"))
      (node (ref "U1") (pin "116") (pinfunction "SDWE_116") (pintype "bidirectional"))
    )
    (net (code "246") (name "SPI_CLK") (class "Default")
      (node (ref "IC6") (pin "2") (pinfunction "SCK_2") (pintype "input"))
      (node (ref "SV1") (pin "25") (pinfunction "25_25") (pintype "passive"))
      (node (ref "U1") (pin "181") (pinfunction "PA2_181") (pintype "bidirectional"))
    )
    (net (code "247") (name "SPI_CSB") (class "Default")
      (node (ref "IC6") (pin "4") (pinfunction "/CS_4") (pintype "input"))
      (node (ref "U1") (pin "182") (pinfunction "PA3_182") (pintype "bidirectional"))
    )
    (net (code "248") (name "SPI_MISO") (class "Default")
      (node (ref "IC6") (pin "8") (pinfunction "SO_8") (pintype "output"))
      (node (ref "SV1") (pin "28") (pinfunction "28_28") (pintype "passive"))
      (node (ref "U1") (pin "179") (pinfunction "PA0_179") (pintype "bidirectional"))
    )
    (net (code "249") (name "SPI_MOSI") (class "Default")
      (node (ref "IC6") (pin "1") (pinfunction "SI_1") (pintype "input"))
      (node (ref "SV1") (pin "27") (pinfunction "27_27") (pintype "passive"))
      (node (ref "U1") (pin "180") (pinfunction "PA1_180") (pintype "bidirectional"))
    )
    (net (code "250") (name "SPI_NSS") (class "Default")
      (node (ref "SV1") (pin "26") (pinfunction "26_26") (pintype "passive"))
      (node (ref "U1") (pin "183") (pinfunction "PA4_183") (pintype "bidirectional"))
    )
    (net (code "251") (name "UART_RXD0") (class "Default")
      (node (ref "SV1") (pin "12") (pinfunction "12_12") (pintype "passive"))
      (node (ref "U1") (pin "21") (pinfunction "PB14_21") (pintype "bidirectional"))
    )
    (net (code "252") (name "UART_RXD1") (class "Default")
      (node (ref "SV1") (pin "16") (pinfunction "16_16") (pintype "passive"))
      (node (ref "U1") (pin "18") (pinfunction "PB7_18") (pintype "bidirectional"))
    )
    (net (code "253") (name "UART_RXD2") (class "Default")
      (node (ref "SV1") (pin "22") (pinfunction "22_22") (pintype "passive"))
      (node (ref "U1") (pin "20") (pinfunction "PB9_20") (pintype "bidirectional"))
    )
    (net (code "254") (name "UART_TXD0") (class "Default")
      (node (ref "SV1") (pin "11") (pinfunction "11_11") (pintype "passive"))
      (node (ref "U1") (pin "22") (pinfunction "PB15_22") (pintype "bidirectional"))
    )
    (net (code "255") (name "UART_TXD1") (class "Default")
      (node (ref "SV1") (pin "15") (pinfunction "15_15") (pintype "passive"))
      (node (ref "U1") (pin "17") (pinfunction "PB6_17") (pintype "bidirectional"))
    )
    (net (code "256") (name "UART_TXD2") (class "Default")
      (node (ref "SV1") (pin "21") (pinfunction "21_21") (pintype "passive"))
      (node (ref "U1") (pin "19") (pinfunction "PB8_19") (pintype "bidirectional"))
    )
    (net (code "257") (name "USBC_DM") (class "Default")
      (node (ref "CON1") (pin "2") (pinfunction "DM_2") (pintype "bidirectional"))
      (node (ref "R5") (pin "1") (pinfunction "1_1") (pintype "passive"))
    )
    (net (code "258") (name "USBC_DP") (class "Default")
      (node (ref "CON1") (pin "3") (pinfunction "DP_3") (pintype "bidirectional"))
      (node (ref "R6") (pin "1") (pinfunction "1_1") (pintype "passive"))
    )
    (net (code "259") (name "USBC_ID") (class "Default")
      (node (ref "CON1") (pin "4") (pinfunction "ID_4") (pintype "bidirectional"))
      (node (ref "R24") (pin "1") (pinfunction "1_1") (pintype "passive"))
      (node (ref "U1") (pin "23") (pinfunction "PB16_23") (pintype "bidirectional"))
    )
    (net (code "260") (name "USBC_PUPD") (class "Default")
      (node (ref "U1") (pin "27") (pinfunction "PB18_27") (pintype "bidirectional"))
    )
    (net (code "261") (name "USBC_VDET") (class "Default")
      (node (ref "R37") (pin "1") (pinfunction "1_1") (pintype "passive"))
      (node (ref "R38") (pin "2") (pinfunction "2_2") (pintype "passive"))
      (node (ref "U1") (pin "26") (pinfunction "PB17_26") (pintype "bidirectional"))
    )
    (net (code "262") (name "USB_C_DM") (class "Default")
      (node (ref "C48") (pin "1") (pinfunction "1_1") (pintype "passive"))
      (node (ref "R5") (pin "2") (pinfunction "2_2") (pintype "passive"))
      (node (ref "U1") (pin "54") (pinfunction "DDM_54") (pintype "bidirectional"))
    )
    (net (code "263") (name "USB_C_DP") (class "Default")
      (node (ref "C49") (pin "1") (pinfunction "1_1") (pintype "passive"))
      (node (ref "R6") (pin "2") (pinfunction "2_2") (pintype "passive"))
      (node (ref "U1") (pin "55") (pinfunction "DDP_55") (pintype "bidirectional"))
    )
    (net (code "264") (name "USB_H1_DM") (class "Default")
      (node (ref "C51") (pin "1") (pinfunction "1_1") (pintype "passive"))
      (node (ref "R10") (pin "2") (pinfunction "2_2") (pintype "passive"))
      (node (ref "R11") (pin "2") (pinfunction "2_2") (pintype "passive"))
      (node (ref "USB") (pin "2") (pinfunction "2_2") (pintype "passive"))
    )
    (net (code "265") (name "USB_H1_DP") (class "Default")
      (node (ref "C52") (pin "1") (pinfunction "1_1") (pintype "passive"))
      (node (ref "R12") (pin "2") (pinfunction "2_2") (pintype "passive"))
      (node (ref "R9") (pin "2") (pinfunction "2_2") (pintype "passive"))
      (node (ref "USB") (pin "3") (pinfunction "3_3") (pintype "passive"))
    )
    (net (code "266") (name "USB_H2_DM") (class "Default")
      (node (ref "USB") (pin "4") (pinfunction "4_4") (pintype "passive"))
    )
    (net (code "267") (name "USB_H2_DP") (class "Default")
      (node (ref "USB") (pin "5") (pinfunction "5_5") (pintype "passive"))
    )
    (net (code "268") (name "USB_VCC") (class "Default")
      (node (ref "C45") (pin "1") (pinfunction "1_1") (pintype "passive"))
      (node (ref "F1") (pin "2") (pinfunction "2_2") (pintype "passive"))
      (node (ref "IC4") (pin "6") (pinfunction "IN2_6") (pintype "bidirectional"))
      (node (ref "J1") (pin "1") (pinfunction "1_1") (pintype "passive"))
      (node (ref "R37") (pin "2") (pinfunction "2_2") (pintype "passive"))
    )
    (net (code "269") (name "VBAT") (class "Default")
      (node (ref "SV1") (pin "4") (pinfunction "4_4") (pintype "passive"))
    )
    (net (code "270") (name "VDDRAM") (class "Default")
      (node (ref "C10") (pin "1") (pinfunction "1_1") (pintype "passive"))
      (node (ref "C11") (pin "1") (pinfunction "1_1") (pintype "passive"))
      (node (ref "C12") (pin "1") (pinfunction "1_1") (pintype "passive"))
      (node (ref "C29") (pin "1") (pinfunction "1_1") (pintype "passive"))
      (node (ref "C30") (pin "1") (pinfunction "1_1") (pintype "passive"))
      (node (ref "C31") (pin "1") (pinfunction "1_1") (pintype "passive"))
      (node (ref "C32") (pin "1") (pinfunction "1_1") (pintype "passive"))
      (node (ref "C33") (pin "1") (pinfunction "1_1") (pintype "passive"))
      (node (ref "C34") (pin "1") (pinfunction "1_1") (pintype "passive"))
      (node (ref "C35") (pin "1") (pinfunction "1_1") (pintype "passive"))
      (node (ref "C36") (pin "1") (pinfunction "1_1") (pintype "passive"))
      (node (ref "C37") (pin "1") (pinfunction "1_1") (pintype "passive"))
      (node (ref "C38") (pin "1") (pinfunction "1_1") (pintype "passive"))
      (node (ref "C39") (pin "1") (pinfunction "1_1") (pintype "passive"))
      (node (ref "C40") (pin "1") (pinfunction "1_1") (pintype "passive"))
      (node (ref "C41") (pin "1") (pinfunction "1_1") (pintype "passive"))
      (node (ref "C42") (pin "1") (pinfunction "1_1") (pintype "passive"))
      (node (ref "C9") (pin "1") (pinfunction "1_1") (pintype "passive"))
      (node (ref "IC1") (pin "1") (pinfunction "VDD_1") (pintype "power_in"))
      (node (ref "IC1") (pin "14") (pinfunction "VDD_14") (pintype "power_in"))
      (node (ref "IC1") (pin "27") (pinfunction "VDD_27") (pintype "power_in"))
      (node (ref "IC1") (pin "3") (pinfunction "VDDQ_3") (pintype "power_in"))
      (node (ref "IC1") (pin "43") (pinfunction "VDDQ_43") (pintype "power_in"))
      (node (ref "IC1") (pin "49") (pinfunction "VDDQ_49") (pintype "power_in"))
      (node (ref "IC1") (pin "9") (pinfunction "VDDQ_9") (pintype "power_in"))
      (node (ref "IC2") (pin "1") (pinfunction "VDD_1") (pintype "power_in"))
      (node (ref "IC2") (pin "14") (pinfunction "VDD_14") (pintype "power_in"))
      (node (ref "IC2") (pin "27") (pinfunction "VDD_27") (pintype "power_in"))
      (node (ref "IC2") (pin "3") (pinfunction "VDDQ_3") (pintype "power_in"))
      (node (ref "IC2") (pin "43") (pinfunction "VDDQ_43") (pintype "power_in"))
      (node (ref "IC2") (pin "49") (pinfunction "VDDQ_49") (pintype "power_in"))
      (node (ref "IC2") (pin "9") (pinfunction "VDDQ_9") (pintype "power_in"))
      (node (ref "R2") (pin "2") (pinfunction "2_2") (pintype "passive"))
      (node (ref "R25") (pin "2") (pinfunction "2_2") (pintype "passive"))
      (node (ref "R26") (pin "1") (pinfunction "1_1") (pintype "passive"))
      (node (ref "U1") (pin "114") (pinfunction "VDDIOM_114") (pintype "bidirectional"))
      (node (ref "U1") (pin "132") (pinfunction "VDDIOM_132") (pintype "bidirectional"))
      (node (ref "U1") (pin "65") (pinfunction "VDDIOM_65") (pintype "bidirectional"))
      (node (ref "U1") (pin "90") (pinfunction "VDDIOM_90") (pintype "bidirectional"))
    )
    (net (code "271") (name "VEXT") (class "Default")
      (node (ref "C47") (pin "1") (pinfunction "1_1") (pintype "passive"))
      (node (ref "IC4") (pin "8") (pinfunction "IN1_8") (pintype "bidirectional"))
      (node (ref "J2") (pin "2") (pinfunction "2_2") (pintype "passive"))
      (node (ref "SV1") (pin "3") (pinfunction "3_3") (pintype "passive"))
    )
    (net (code "272") (name "unconnected-(IC1A-NC-Pad40)") (class "Default")
      (node (ref "IC1") (pin "40") (pinfunction "NC_40") (pintype "no_connect"))
    )
    (net (code "273") (name "unconnected-(IC2A-NC-Pad40)") (class "Default")
      (node (ref "IC2") (pin "40") (pinfunction "NC_40") (pintype "no_connect"))
    )
    (net (code "274") (name "unconnected-(IC4-Pad1)") (class "Default")
      (node (ref "IC4") (pin "1") (pinfunction "1_1") (pintype "bidirectional"))
    )
    (net (code "275") (name "unconnected-(IC4-Pad2)") (class "Default")
      (node (ref "IC4") (pin "2") (pinfunction "2_2") (pintype "bidirectional"))
    )
    (net (code "276") (name "unconnected-(RECV-PadTP)") (class "Default")
      (node (ref "RECV") (pin "TP") (pinfunction "TP_TP") (pintype "input"))
    )
    (net (code "277") (name "unconnected-(SV1-Pad5)") (class "Default")
      (node (ref "SV1") (pin "5") (pinfunction "5_5") (pintype "passive"))
    )
    (net (code "278") (name "unconnected-(SV1-Pad6)") (class "Default")
      (node (ref "SV1") (pin "6") (pinfunction "6_6") (pintype "passive"))
    )
    (net (code "279") (name "unconnected-(SV1-Pad8)") (class "Default")
      (node (ref "SV1") (pin "8") (pinfunction "8_8") (pintype "passive"))
    )
    (net (code "280") (name "unconnected-(SV1-Pad9)") (class "Default")
      (node (ref "SV1") (pin "9") (pinfunction "9_9") (pintype "passive"))
    )
    (net (code "281") (name "unconnected-(SV1-Pad10)") (class "Default")
      (node (ref "SV1") (pin "10") (pinfunction "10_10") (pintype "passive"))
    )
    (net (code "282") (name "unconnected-(U1B-PB0-Pad9)") (class "Default")
      (node (ref "U1") (pin "9") (pinfunction "PB0_9") (pintype "bidirectional"))
    )
    (net (code "283") (name "unconnected-(U1B-PB1-Pad10)") (class "Default")
      (node (ref "U1") (pin "10") (pinfunction "PB1_10") (pintype "bidirectional"))
    )
    (net (code "284") (name "unconnected-(U1B-PB2-Pad11)") (class "Default")
      (node (ref "U1") (pin "11") (pinfunction "PB2_11") (pintype "bidirectional"))
    )
    (net (code "285") (name "unconnected-(U1B-PB3-Pad12)") (class "Default")
      (node (ref "U1") (pin "12") (pinfunction "PB3_12") (pintype "bidirectional"))
    )
    (net (code "286") (name "unconnected-(U1B-PB4-Pad15)") (class "Default")
      (node (ref "U1") (pin "15") (pinfunction "PB4_15") (pintype "bidirectional"))
    )
    (net (code "287") (name "unconnected-(U1B-PB22-Pad165)") (class "Default")
      (node (ref "U1") (pin "165") (pinfunction "PB22_165") (pintype "bidirectional"))
    )
    (net (code "288") (name "unconnected-(U1B-PB23-Pad166)") (class "Default")
      (node (ref "U1") (pin "166") (pinfunction "PB23_166") (pintype "bidirectional"))
    )
    (net (code "289") (name "unconnected-(U1B-PB24-Pad167)") (class "Default")
      (node (ref "U1") (pin "167") (pinfunction "PB24_167") (pintype "bidirectional"))
    )
    (net (code "290") (name "unconnected-(U1B-PB25-Pad168)") (class "Default")
      (node (ref "U1") (pin "168") (pinfunction "PB25_168") (pintype "bidirectional"))
    )
    (net (code "291") (name "unconnected-(U1B-PB26-Pad171)") (class "Default")
      (node (ref "U1") (pin "171") (pinfunction "PB26_171") (pintype "bidirectional"))
    )
    (net (code "292") (name "unconnected-(U1B-PB27-Pad172)") (class "Default")
      (node (ref "U1") (pin "172") (pinfunction "PB27_172") (pintype "bidirectional"))
    )
    (net (code "293") (name "unconnected-(U1B-PB28-Pad175)") (class "Default")
      (node (ref "U1") (pin "175") (pinfunction "PB28_175") (pintype "bidirectional"))
    )
    (net (code "294") (name "unconnected-(U1B-PB29-Pad176)") (class "Default")
      (node (ref "U1") (pin "176") (pinfunction "PB29_176") (pintype "bidirectional"))
    )
    (net (code "295") (name "unconnected-(U1B-PB30-Pad177)") (class "Default")
      (node (ref "U1") (pin "177") (pinfunction "PB30_177") (pintype "bidirectional"))
    )
    (net (code "296") (name "unconnected-(U1B-PB31-Pad178)") (class "Default")
      (node (ref "U1") (pin "178") (pinfunction "PB31_178") (pintype "bidirectional"))
    )
    (net (code "297") (name "unconnected-(U1C-PC4-Pad62)") (class "Default")
      (node (ref "U1") (pin "62") (pinfunction "PC4_62") (pintype "bidirectional"))
    )
    (net (code "298") (name "unconnected-(U1C-PC5-Pad67)") (class "Default")
      (node (ref "U1") (pin "67") (pinfunction "PC5_67") (pintype "bidirectional"))
    )
    (net (code "299") (name "unconnected-(U1C-PC8-Pad61)") (class "Default")
      (node (ref "U1") (pin "61") (pinfunction "PC8_61") (pintype "bidirectional"))
    )
    (net (code "300") (name "unconnected-(U1C-PC10-Pad58)") (class "Default")
      (node (ref "U1") (pin "58") (pinfunction "PC10_58") (pintype "bidirectional"))
    )
    (net (code "301") (name "unconnected-(U1C-PC11-Pad57)") (class "Default")
      (node (ref "U1") (pin "57") (pinfunction "PC11_57") (pintype "bidirectional"))
    )
    (net (code "302") (name "unconnected-(U1D-A12-Pad85)") (class "Default")
      (node (ref "U1") (pin "85") (pinfunction "A12_85") (pintype "bidirectional"))
    )
    (net (code "303") (name "unconnected-(U1D-A15-Pad82)") (class "Default")
      (node (ref "U1") (pin "82") (pinfunction "A15_82") (pintype "bidirectional"))
    )
    (net (code "304") (name "unconnected-(U1D-A18-Pad79)") (class "Default")
      (node (ref "U1") (pin "79") (pinfunction "A18_79") (pintype "bidirectional"))
    )
    (net (code "305") (name "unconnected-(U1D-A19-Pad76)") (class "Default")
      (node (ref "U1") (pin "76") (pinfunction "A19_76") (pintype "bidirectional"))
    )
    (net (code "306") (name "unconnected-(U1D-A20-Pad75)") (class "Default")
      (node (ref "U1") (pin "75") (pinfunction "A20_75") (pintype "bidirectional"))
    )
    (net (code "307") (name "unconnected-(U1D-A21-Pad74)") (class "Default")
      (node (ref "U1") (pin "74") (pinfunction "A21_74") (pintype "bidirectional"))
    )
    (net (code "308") (name "unconnected-(U1D-A22-Pad73)") (class "Default")
      (node (ref "U1") (pin "73") (pinfunction "A22_73") (pintype "bidirectional"))
    )
    (net (code "309") (name "unconnected-(U1D-CFOE{slash}NRD-Pad69)") (class "Default")
      (node (ref "U1") (pin "69") (pinfunction "CFOE/NRD_69") (pintype "bidirectional"))
    )
    (net (code "310") (name "unconnected-(U1D-CFWE{slash}NWE-Pad70)") (class "Default")
      (node (ref "U1") (pin "70") (pinfunction "CFWE/NWE_70") (pintype "bidirectional"))
    )
    (net (code "311") (name "unconnected-(U1D-NANDOE-Pad71)") (class "Default")
      (node (ref "U1") (pin "71") (pinfunction "NANDOE_71") (pintype "bidirectional"))
    )
    (net (code "312") (name "unconnected-(U1D-NANDWE-Pad72)") (class "Default")
      (node (ref "U1") (pin "72") (pinfunction "NANDWE_72") (pintype "bidirectional"))
    )
    (net (code "313") (name "unconnected-(U1D-NCS0-Pad68)") (class "Default")
      (node (ref "U1") (pin "68") (pinfunction "NCS0_68") (pintype "bidirectional"))
    )
    (net (code "314") (name "unconnected-(U1F-NC-Pad152)") (class "Default")
      (node (ref "U1") (pin "152") (pinfunction "NC_152") (pintype "no_connect"))
    )
    (net (code "315") (name "unconnected-(U1F-NTRST-Pad35)") (class "Default")
      (node (ref "U1") (pin "35") (pinfunction "NTRST_35") (pintype "bidirectional"))
    )
    (net (code "316") (name "unconnected-(U1F-RTCK-Pad37)") (class "Default")
      (node (ref "U1") (pin "37") (pinfunction "RTCK_37") (pintype "bidirectional"))
    )
    (net (code "317") (name "unconnected-(U1F-SHDN-Pad49)") (class "Default")
      (node (ref "U1") (pin "49") (pinfunction "SHDN_49") (pintype "bidirectional"))
    )
    (net (code "318") (name "unconnected-(U1F-TCK-Pad34)") (class "Default")
      (node (ref "U1") (pin "34") (pinfunction "TCK_34") (pintype "bidirectional"))
    )
    (net (code "319") (name "unconnected-(U1F-TDI-Pad30)") (class "Default")
      (node (ref "U1") (pin "30") (pinfunction "TDI_30") (pintype "bidirectional"))
    )
    (net (code "320") (name "unconnected-(U1F-TDO-Pad29)") (class "Default")
      (node (ref "U1") (pin "29") (pinfunction "TDO_29") (pintype "bidirectional"))
    )
    (net (code "321") (name "unconnected-(U1F-TMS-Pad31)") (class "Default")
      (node (ref "U1") (pin "31") (pinfunction "TMS_31") (pintype "bidirectional"))
    )
    (net (code "322") (name "unconnected-(X1-Pad2)") (class "Default")
      (node (ref "X1") (pin "2") (pinfunction "2_2") (pintype "passive"))
    )
    (net (code "323") (name "unconnected-(X2-Pad6)") (class "Default")
      (node (ref "X2") (pin "6") (pinfunction "6_6") (pintype "passive"))
    )
    (net (code "324") (name "~{RST}") (class "Default")
      (node (ref "!RST") (pin "TP") (pinfunction "TP_TP") (pintype "input"))
      (node (ref "IC6") (pin "3") (pinfunction "/RST_3") (pintype "input"))
      (node (ref "R4") (pin "2") (pinfunction "2_2") (pintype "passive"))
      (node (ref "SV1") (pin "7") (pinfunction "7_7") (pintype "passive"))
      (node (ref "U1") (pin "36") (pinfunction "NRST_36") (pintype "bidirectional"))
    )
    (net (code "325") (name "~{WKUP}") (class "Default")
      (node (ref "!WKUP") (pin "TP") (pinfunction "TP_TP") (pintype "input"))
      (node (ref "U1") (pin "48") (pinfunction "WKUP_48") (pintype "bidirectional"))
    )
  )
)
